# CPU_DRAM.net
KiCad netlist of a schematic drawn in Altium Designer
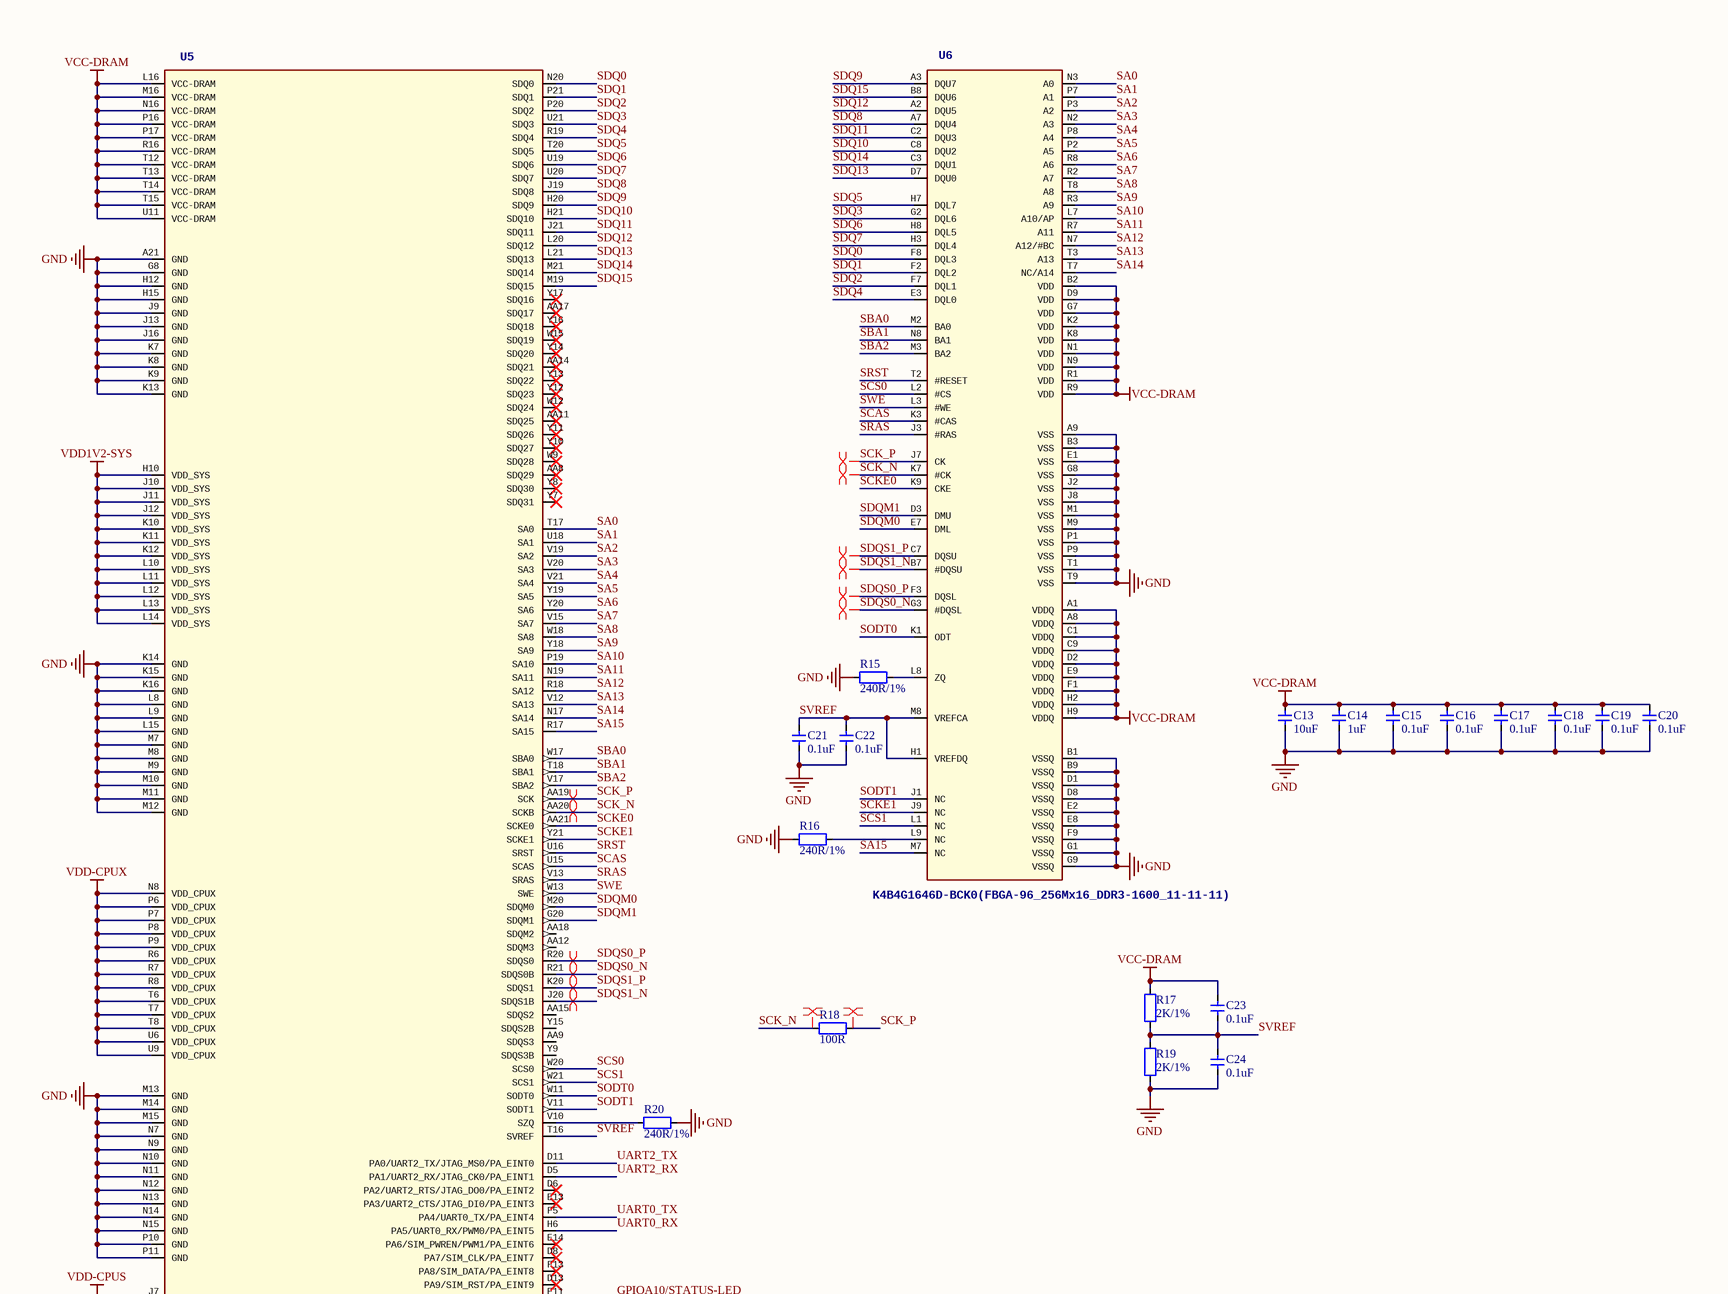
[diagram p0: CPU&DRAM.SchDoc, top]
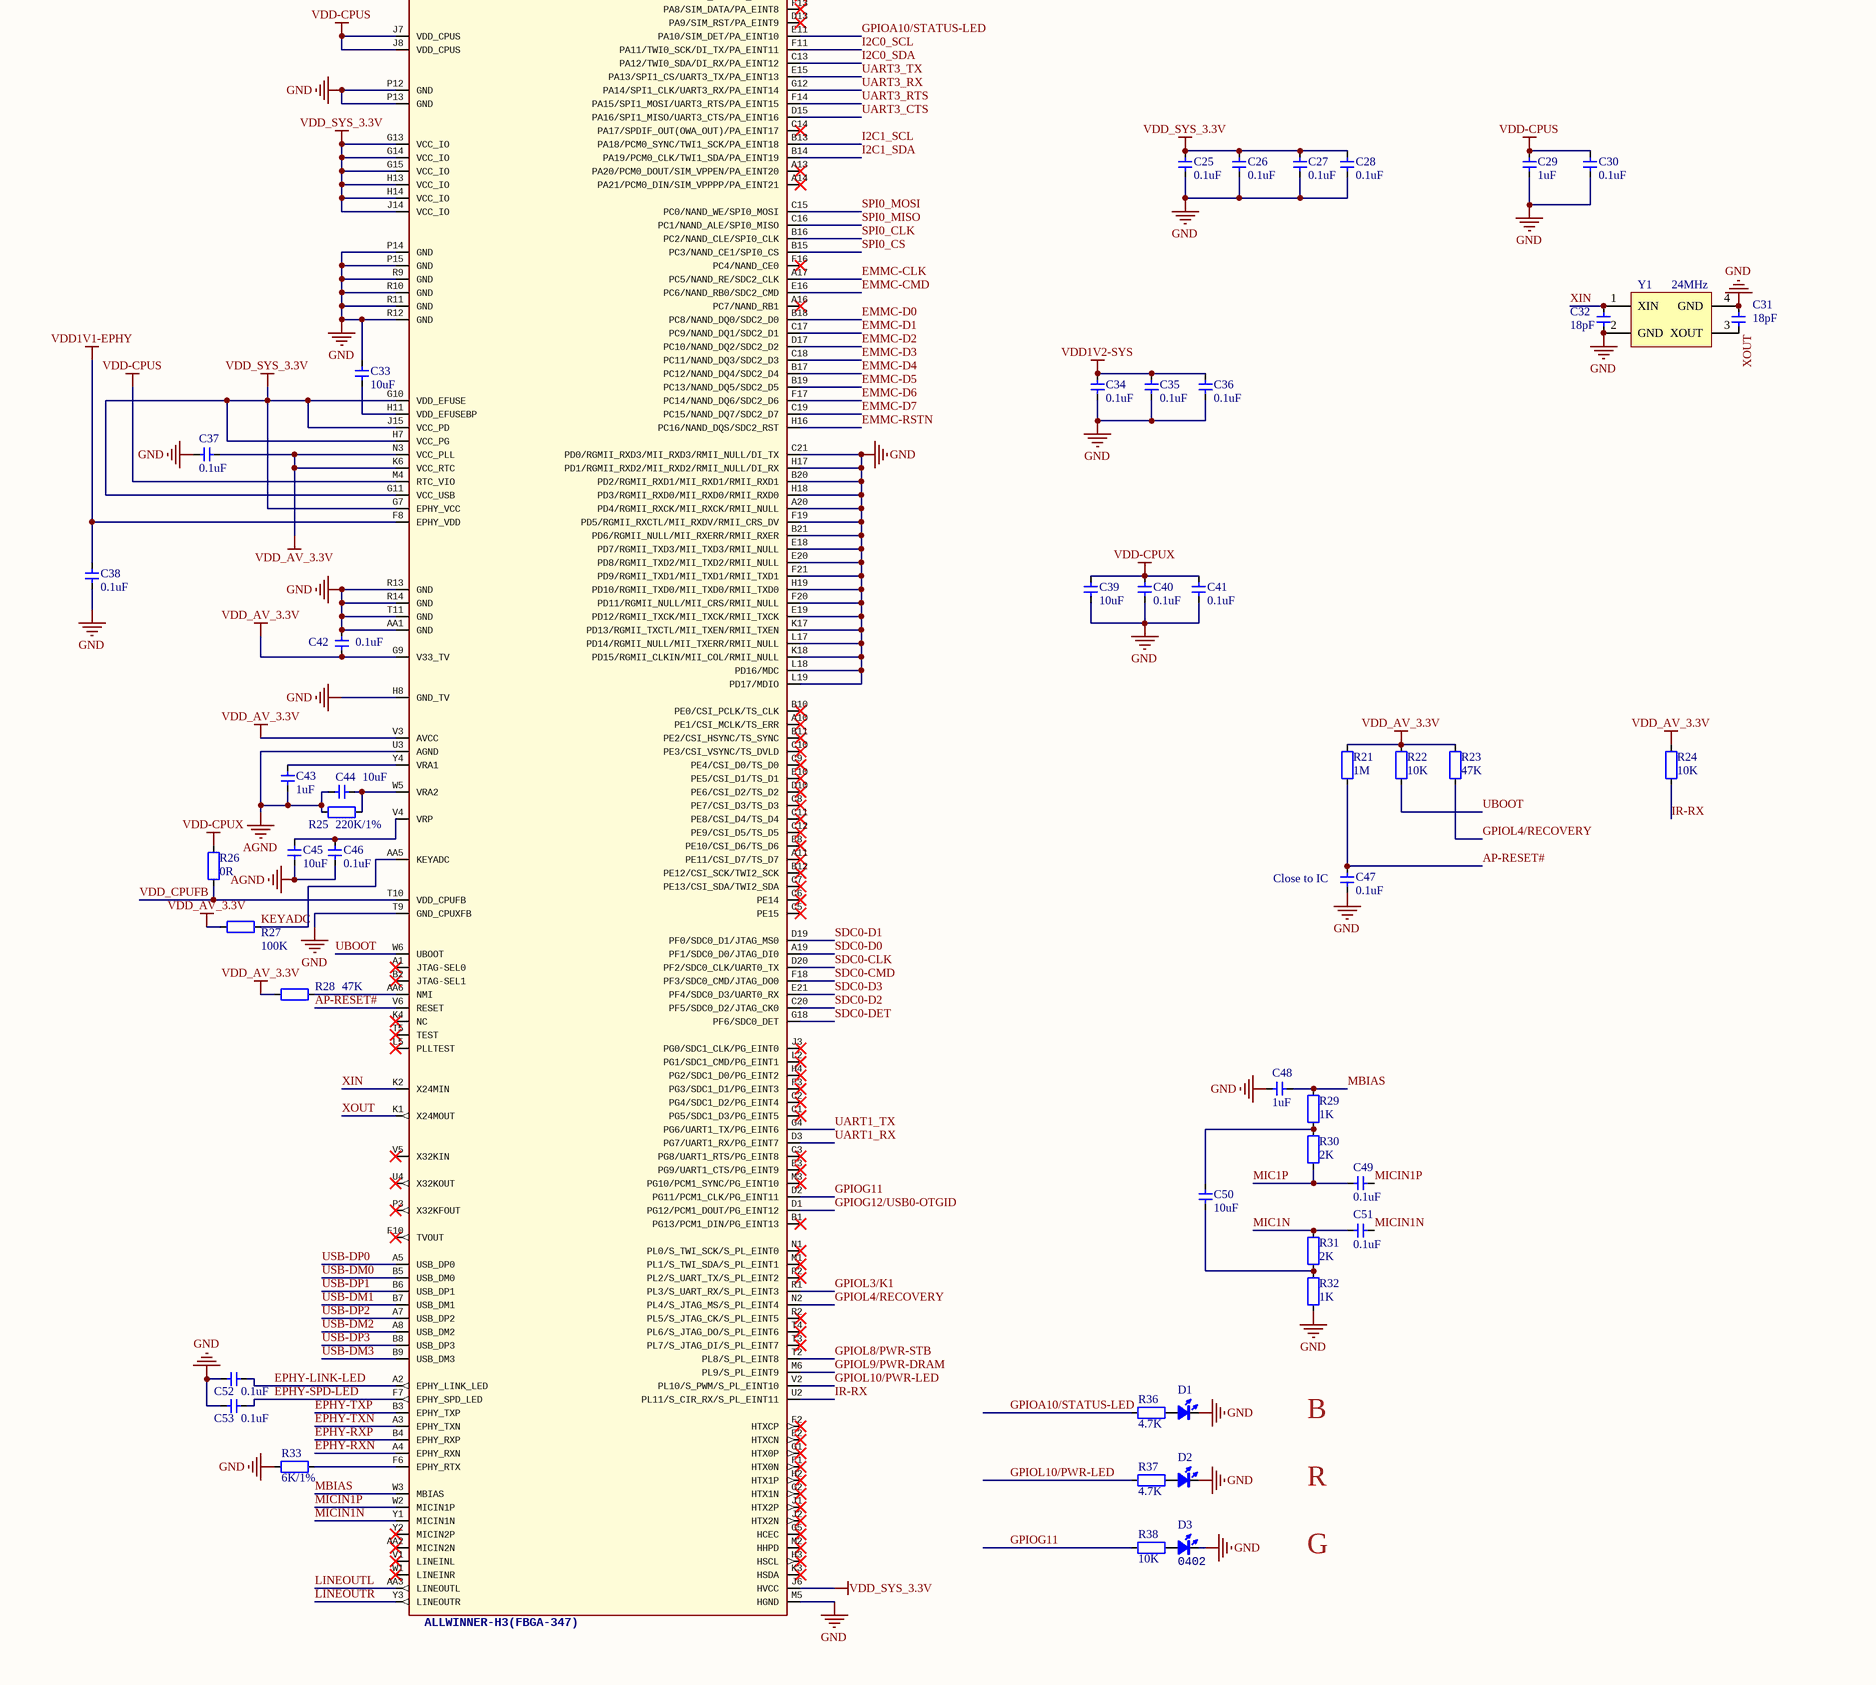
[diagram p1: CPU&DRAM.SchDoc, bottom]

(export (version "E")
  (design (tool "Eeschema 10.0.6"))
  (components
    (comp (ref "C13")
      (value "10uF")
      (footprint "CAP_0402")
      (description "Capacitor")
      (libsource (lib "MyPcbLib") (part "电容-0402"))
    )
    (comp (ref "C14")
      (value "1uF")
      (footprint "CAP_0402")
      (description "Capacitor")
      (libsource (lib "MyPcbLib") (part "电容-0402"))
    )
    (comp (ref "C15")
      (value "0.1uF")
      (footprint "CAP_0402")
      (description "Capacitor")
      (libsource (lib "MyPcbLib") (part "电容-0402"))
    )
    (comp (ref "C16")
      (value "0.1uF")
      (footprint "CAP_0402")
      (description "Capacitor")
      (libsource (lib "MyPcbLib") (part "电容-0402"))
    )
    (comp (ref "C17")
      (value "0.1uF")
      (footprint "CAP_0402")
      (description "Capacitor")
      (libsource (lib "MyPcbLib") (part "电容-0402"))
    )
    (comp (ref "C18")
      (value "0.1uF")
      (footprint "CAP_0402")
      (description "Capacitor")
      (libsource (lib "MyPcbLib") (part "电容-0402"))
    )
    (comp (ref "C19")
      (value "0.1uF")
      (footprint "CAP_0402")
      (description "Capacitor")
      (libsource (lib "MyPcbLib") (part "电容-0402"))
    )
    (comp (ref "C20")
      (value "0.1uF")
      (footprint "CAP_0402")
      (description "Capacitor")
      (libsource (lib "MyPcbLib") (part "电容-0402"))
    )
    (comp (ref "C21")
      (value "0.1uF")
      (footprint "CAP_0402")
      (description "Capacitor")
      (libsource (lib "MyPcbLib") (part "电容-0402"))
    )
    (comp (ref "C22")
      (value "0.1uF")
      (footprint "CAP_0402")
      (description "Capacitor")
      (libsource (lib "MyPcbLib") (part "电容-0402"))
    )
    (comp (ref "C23")
      (value "0.1uF")
      (footprint "CAP_0402")
      (description "Capacitor")
      (libsource (lib "MyPcbLib") (part "电容-0402"))
    )
    (comp (ref "C24")
      (value "0.1uF")
      (footprint "CAP_0402")
      (description "Capacitor")
      (libsource (lib "MyPcbLib") (part "电容-0402"))
    )
    (comp (ref "C25")
      (value "0.1uF")
      (footprint "CAP_0402")
      (description "Capacitor")
      (libsource (lib "MyPcbLib") (part "电容-0402"))
    )
    (comp (ref "C26")
      (value "0.1uF")
      (footprint "CAP_0402")
      (description "Capacitor")
      (libsource (lib "MyPcbLib") (part "电容-0402"))
    )
    (comp (ref "C27")
      (value "0.1uF")
      (footprint "CAP_0402")
      (description "Capacitor")
      (libsource (lib "MyPcbLib") (part "电容-0402"))
    )
    (comp (ref "C28")
      (value "0.1uF")
      (footprint "CAP_0402")
      (description "Capacitor")
      (libsource (lib "MyPcbLib") (part "电容-0402"))
    )
    (comp (ref "C29")
      (value "1uF")
      (footprint "CAP_0402")
      (description "Capacitor")
      (libsource (lib "MyPcbLib") (part "电容-0402"))
    )
    (comp (ref "C30")
      (value "0.1uF")
      (footprint "CAP_0402")
      (description "Capacitor")
      (libsource (lib "MyPcbLib") (part "电容-0402"))
    )
    (comp (ref "C31")
      (value "18pF")
      (footprint "CAP_0402")
      (description "Capacitor")
      (libsource (lib "MyPcbLib") (part "电容-0402"))
    )
    (comp (ref "C32")
      (value "18pF")
      (footprint "CAP_0402")
      (description "Capacitor")
      (libsource (lib "MyPcbLib") (part "电容-0402"))
    )
    (comp (ref "C33")
      (value "10uF")
      (footprint "CAP_0402")
      (description "Capacitor")
      (libsource (lib "MyPcbLib") (part "电容-0402"))
    )
    (comp (ref "C34")
      (value "0.1uF")
      (footprint "CAP_0402")
      (description "Capacitor")
      (libsource (lib "MyPcbLib") (part "电容-0402"))
    )
    (comp (ref "C35")
      (value "0.1uF")
      (footprint "CAP_0402")
      (description "Capacitor")
      (libsource (lib "MyPcbLib") (part "电容-0402"))
    )
    (comp (ref "C36")
      (value "0.1uF")
      (footprint "CAP_0402")
      (description "Capacitor")
      (libsource (lib "MyPcbLib") (part "电容-0402"))
    )
    (comp (ref "C37")
      (value "0.1uF")
      (footprint "CAP_0402")
      (description "Capacitor")
      (libsource (lib "MyPcbLib") (part "电容-0402"))
    )
    (comp (ref "C38")
      (value "0.1uF")
      (footprint "CAP_0402")
      (description "Capacitor")
      (libsource (lib "MyPcbLib") (part "电容-0402"))
    )
    (comp (ref "C39")
      (value "10uF")
      (footprint "CAP_0402")
      (description "Capacitor")
      (libsource (lib "MyPcbLib") (part "电容-0402"))
    )
    (comp (ref "C40")
      (value "0.1uF")
      (footprint "CAP_0402")
      (description "Capacitor")
      (libsource (lib "MyPcbLib") (part "电容-0402"))
    )
    (comp (ref "C41")
      (value "0.1uF")
      (footprint "CAP_0402")
      (description "Capacitor")
      (libsource (lib "MyPcbLib") (part "电容-0402"))
    )
    (comp (ref "C42")
      (value "0.1uF")
      (footprint "CAP_0402")
      (description "Capacitor")
      (libsource (lib "MyPcbLib") (part "电容-0402"))
    )
    (comp (ref "C43")
      (value "1uF")
      (footprint "CAP_0402")
      (description "Capacitor")
      (libsource (lib "MyPcbLib") (part "电容-0402"))
    )
    (comp (ref "C44")
      (value "10uF")
      (footprint "CAP_0402")
      (description "Capacitor")
      (libsource (lib "MyPcbLib") (part "电容-0402"))
    )
    (comp (ref "C45")
      (value "10uF")
      (footprint "CAP_0402")
      (description "Capacitor")
      (libsource (lib "MyPcbLib") (part "电容-0402"))
    )
    (comp (ref "C46")
      (value "0.1uF")
      (footprint "CAP_0402")
      (description "Capacitor")
      (libsource (lib "MyPcbLib") (part "电容-0402"))
    )
    (comp (ref "C47")
      (value "0.1uF")
      (footprint "CAP_0402")
      (description "Capacitor")
      (libsource (lib "MyPcbLib") (part "电容-0402"))
    )
    (comp (ref "C48")
      (value "1uF")
      (footprint "CAP_0402")
      (description "Capacitor")
      (libsource (lib "MyPcbLib") (part "电容-0402"))
    )
    (comp (ref "C49")
      (value "0.1uF")
      (footprint "CAP_0402")
      (description "Capacitor")
      (libsource (lib "MyPcbLib") (part "电容-0402"))
    )
    (comp (ref "C50")
      (value "10uF")
      (footprint "CAP_0402")
      (description "Capacitor")
      (libsource (lib "MyPcbLib") (part "电容-0402"))
    )
    (comp (ref "C51")
      (value "0.1uF")
      (footprint "CAP_0402")
      (description "Capacitor")
      (libsource (lib "MyPcbLib") (part "电容-0402"))
    )
    (comp (ref "C52")
      (value "0.1uF")
      (footprint "CAP_0402")
      (description "Capacitor")
      (libsource (lib "MyPcbLib") (part "电容-0402"))
    )
    (comp (ref "C53")
      (value "0.1uF")
      (footprint "CAP_0402")
      (description "Capacitor")
      (libsource (lib "MyPcbLib") (part "电容-0402"))
    )
    (comp (ref "D1")
      (value "color?")
      (footprint "LED_0402_BLUE")
      (description "LED")
      (libsource (lib "KitSprout") (part "LED_0402"))
    )
    (comp (ref "D2")
      (value "color?")
      (footprint "LED_0402_RED")
      (description "LED")
      (libsource (lib "KitSprout") (part "LED_0402"))
    )
    (comp (ref "D3")
      (value "color?")
      (footprint "LED_0402_G")
      (description "LED")
      (fields (field (name "TYPE") "0402"))
      (libsource (lib "KitSprout") (part "LED_0402"))
    )
    (comp (ref "R15")
      (value "240R/1%")
      (footprint "RES_0402")
      (description "Resistor")
      (libsource (lib "") (part "电阻-0402_1"))
    )
    (comp (ref "R16")
      (value "240R/1%")
      (footprint "RES_0402")
      (description "Resistor")
      (libsource (lib "") (part "电阻-0402_1"))
    )
    (comp (ref "R17")
      (value "2K/1%")
      (footprint "RES_0402")
      (description "Resistor")
      (libsource (lib "MyPcbLib") (part "电阻-0402"))
    )
    (comp (ref "R18")
      (value "100R")
      (footprint "RES_0402")
      (description "Resistor")
      (libsource (lib "") (part "电阻-0402_2"))
    )
    (comp (ref "R19")
      (value "2K/1%")
      (footprint "RES_0402")
      (description "Resistor")
      (libsource (lib "MyPcbLib") (part "电阻-0402"))
    )
    (comp (ref "R20")
      (value "240R/1%")
      (footprint "RES_0402")
      (description "Resistor")
      (libsource (lib "") (part "电阻-0402_2"))
    )
    (comp (ref "R21")
      (value "1M")
      (footprint "RES_0402")
      (description "Resistor")
      (libsource (lib "MyPcbLib") (part "电阻-0402"))
    )
    (comp (ref "R22")
      (value "10K")
      (footprint "RES_0402")
      (description "Resistor")
      (libsource (lib "MyPcbLib") (part "电阻-0402"))
    )
    (comp (ref "R23")
      (value "47K")
      (footprint "RES_0402")
      (description "Resistor")
      (libsource (lib "MyPcbLib") (part "电阻-0402"))
    )
    (comp (ref "R24")
      (value "10K")
      (footprint "RES_0402")
      (description "Resistor")
      (libsource (lib "MyPcbLib") (part "电阻-0402"))
    )
    (comp (ref "R25")
      (value "220K/1%")
      (footprint "RES_0402")
      (description "Resistor")
      (libsource (lib "") (part "电阻-0402_2"))
    )
    (comp (ref "R26")
      (value "0R")
      (footprint "RES_0402")
      (description "Resistor")
      (libsource (lib "MyPcbLib") (part "电阻-0402"))
    )
    (comp (ref "R27")
      (value "100K")
      (footprint "RES_0402")
      (description "Resistor")
      (libsource (lib "") (part "电阻-0402_2"))
    )
    (comp (ref "R28")
      (value "47K")
      (footprint "RES_0402")
      (description "Resistor")
      (libsource (lib "") (part "电阻-0402_2"))
    )
    (comp (ref "R29")
      (value "1K")
      (footprint "RES_0402")
      (description "Resistor")
      (libsource (lib "MyPcbLib") (part "电阻-0402"))
    )
    (comp (ref "R30")
      (value "2K")
      (footprint "RES_0402")
      (description "Resistor")
      (libsource (lib "MyPcbLib") (part "电阻-0402"))
    )
    (comp (ref "R31")
      (value "2K")
      (footprint "RES_0402")
      (description "Resistor")
      (libsource (lib "MyPcbLib") (part "电阻-0402"))
    )
    (comp (ref "R32")
      (value "1K")
      (footprint "RES_0402")
      (description "Resistor")
      (libsource (lib "MyPcbLib") (part "电阻-0402"))
    )
    (comp (ref "R33")
      (value "6K/1%")
      (footprint "RES_0402")
      (description "Resistor")
      (libsource (lib "") (part "电阻-0402_2"))
    )
    (comp (ref "R36")
      (value "4.7K")
      (footprint "RES_0402")
      (description "Resistor")
      (libsource (lib "") (part "电阻-0402_2"))
    )
    (comp (ref "R37")
      (value "4.7K")
      (footprint "RES_0402")
      (description "Resistor")
      (libsource (lib "") (part "电阻-0402_2"))
    )
    (comp (ref "R38")
      (value "10K")
      (footprint "RES_0402")
      (description "Resistor")
      (libsource (lib "") (part "电阻-0402_2"))
    )
    (comp (ref "U5")
      (value "ALLWINNER-H3(FBGA-347)")
      (footprint "FBGA-347 - duplicate")
      (libsource (lib "mLib") (part "ALLWINNER-H3(FBGA-347)"))
    )
    (comp (ref "U6")
      (value "K4B4G1646D-BCK0(FBGA-96_256Mx16_DDR3-1600_11-11-11)")
      (footprint "FBGA96(HYNIX_SAMSUNG_512MX16_DDR3)")
      (libsource (lib "mLib") (part "K4B8G1646Q-MYK0(FBGA-96_512MX16_DDR3-1600)"))
    )
    (comp (ref "Y1")
      (value "24MHz")
      (footprint "晶振2520")
      (description "2520无源")
      (fields (field (name "MF") "ECS International") (field (name "MP") "ECS-3225S30-240-EN-TR"))
      (libsource (lib "MyPcbLib") (part "晶振-4Pin-无源"))
    )
  )
  (nets
    (net (code "1") (name "/AP-RESET#") (class "Default")
      (node (ref "C47") (pin "2") (pinfunction "2_2") (pintype "passive"))
      (node (ref "R21") (pin "1") (pinfunction "1_1") (pintype "passive"))
      (node (ref "U5") (pin "V6") (pinfunction "RESET_V6") (pintype "passive"))
    )
    (net (code "2") (name "/EMMC-CLK") (class "Default")
      (node (ref "U5") (pin "A17") (pinfunction "PC5/NAND_RE/SDC2_CLK_A17") (pintype "passive"))
    )
    (net (code "3") (name "/EMMC-CMD") (class "Default")
      (node (ref "U5") (pin "E16") (pinfunction "PC6/NAND_RB0/SDC2_CMD_E16") (pintype "passive"))
    )
    (net (code "4") (name "/EMMC-D0") (class "Default")
      (node (ref "U5") (pin "B18") (pinfunction "PC8/NAND_DQ0/SDC2_D0_B18") (pintype "passive"))
    )
    (net (code "5") (name "/EMMC-D1") (class "Default")
      (node (ref "U5") (pin "C17") (pinfunction "PC9/NAND_DQ1/SDC2_D1_C17") (pintype "passive"))
    )
    (net (code "6") (name "/EMMC-D2") (class "Default")
      (node (ref "U5") (pin "D17") (pinfunction "PC10/NAND_DQ2/SDC2_D2_D17") (pintype "passive"))
    )
    (net (code "7") (name "/EMMC-D3") (class "Default")
      (node (ref "U5") (pin "C18") (pinfunction "PC11/NAND_DQ3/SDC2_D3_C18") (pintype "passive"))
    )
    (net (code "8") (name "/EMMC-D4") (class "Default")
      (node (ref "U5") (pin "B17") (pinfunction "PC12/NAND_DQ4/SDC2_D4_B17") (pintype "passive"))
    )
    (net (code "9") (name "/EMMC-D5") (class "Default")
      (node (ref "U5") (pin "B19") (pinfunction "PC13/NAND_DQ5/SDC2_D5_B19") (pintype "passive"))
    )
    (net (code "10") (name "/EMMC-D6") (class "Default")
      (node (ref "U5") (pin "F17") (pinfunction "PC14/NAND_DQ6/SDC2_D6_F17") (pintype "passive"))
    )
    (net (code "11") (name "/EMMC-D7") (class "Default")
      (node (ref "U5") (pin "C19") (pinfunction "PC15/NAND_DQ7/SDC2_D7_C19") (pintype "passive"))
    )
    (net (code "12") (name "/EMMC-RSTN") (class "Default")
      (node (ref "U5") (pin "H16") (pinfunction "PC16/NAND_DQS/SDC2_RST_H16") (pintype "passive"))
    )
    (net (code "13") (name "/EPHY-LINK-LED") (class "Default")
      (node (ref "C52") (pin "2") (pinfunction "2_2") (pintype "passive"))
      (node (ref "U5") (pin "A2") (pinfunction "EPHY_LINK_LED_A2") (pintype "output"))
    )
    (net (code "14") (name "/EPHY-RXN") (class "Default")
      (node (ref "U5") (pin "A4") (pinfunction "EPHY_RXN_A4") (pintype "passive"))
    )
    (net (code "15") (name "/EPHY-RXP") (class "Default")
      (node (ref "U5") (pin "B4") (pinfunction "EPHY_RXP_B4") (pintype "passive"))
    )
    (net (code "16") (name "/EPHY-SPD-LED") (class "Default")
      (node (ref "C53") (pin "2") (pinfunction "2_2") (pintype "passive"))
      (node (ref "U5") (pin "F7") (pinfunction "EPHY_SPD_LED_F7") (pintype "output"))
    )
    (net (code "17") (name "/EPHY-TXN") (class "Default")
      (node (ref "U5") (pin "A3") (pinfunction "EPHY_TXN_A3") (pintype "passive"))
    )
    (net (code "18") (name "/EPHY-TXP") (class "Default")
      (node (ref "U5") (pin "B3") (pinfunction "EPHY_TXP_B3") (pintype "passive"))
    )
    (net (code "19") (name "/GPIOA10{slash}STATUS-LED") (class "Default")
      (node (ref "R36") (pin "1") (pinfunction "1_1") (pintype "passive"))
      (node (ref "U5") (pin "E11") (pinfunction "PA10/SIM_DET/PA_EINT10_E11") (pintype "passive"))
    )
    (net (code "20") (name "/GPIOG11") (class "Default")
      (node (ref "R38") (pin "1") (pinfunction "1_1") (pintype "passive"))
      (node (ref "U5") (pin "D2") (pinfunction "PG11/PCM1_CLK/PG_EINT11_D2") (pintype "passive"))
    )
    (net (code "21") (name "/GPIOG12{slash}USB0-OTGID") (class "Default")
      (node (ref "U5") (pin "D1") (pinfunction "PG12/PCM1_DOUT/PG_EINT12_D1") (pintype "passive"))
    )
    (net (code "22") (name "/GPIOL3{slash}K1") (class "Default")
      (node (ref "U5") (pin "R1") (pinfunction "PL3/S_UART_RX/S_PL_EINT3_R1") (pintype "passive"))
    )
    (net (code "23") (name "/GPIOL4{slash}RECOVERY") (class "Default")
      (node (ref "R23") (pin "1") (pinfunction "1_1") (pintype "passive"))
      (node (ref "U5") (pin "N2") (pinfunction "PL4/S_JTAG_MS/S_PL_EINT4_N2") (pintype "passive"))
    )
    (net (code "24") (name "/GPIOL8{slash}PWR-STB") (class "Default")
      (node (ref "U5") (pin "T2") (pinfunction "PL8/S_PL_EINT8_T2") (pintype "passive"))
    )
    (net (code "25") (name "/GPIOL9{slash}PWR-DRAM") (class "Default")
      (node (ref "U5") (pin "M6") (pinfunction "PL9/S_PL_EINT9_M6") (pintype "passive"))
    )
    (net (code "26") (name "/GPIOL10{slash}PWR-LED") (class "Default")
      (node (ref "R37") (pin "1") (pinfunction "1_1") (pintype "passive"))
      (node (ref "U5") (pin "V2") (pinfunction "PL10/S_PWM/S_PL_EINT10_V2") (pintype "passive"))
    )
    (net (code "27") (name "/I2C0_SCL") (class "Default")
      (node (ref "U5") (pin "F11") (pinfunction "PA11/TWI0_SCK/DI_TX/PA_EINT11_F11") (pintype "passive"))
    )
    (net (code "28") (name "/I2C0_SDA") (class "Default")
      (node (ref "U5") (pin "C13") (pinfunction "PA12/TWI0_SDA/DI_RX/PA_EINT12_C13") (pintype "passive"))
    )
    (net (code "29") (name "/I2C1_SCL") (class "Default")
      (node (ref "U5") (pin "B13") (pinfunction "PA18/PCM0_SYNC/TWI1_SCK/PA_EINT18_B13") (pintype "passive"))
    )
    (net (code "30") (name "/I2C1_SDA") (class "Default")
      (node (ref "U5") (pin "B14") (pinfunction "PA19/PCM0_CLK/TWI1_SDA/PA_EINT19_B14") (pintype "passive"))
    )
    (net (code "31") (name "/IR-RX") (class "Default")
      (node (ref "R24") (pin "1") (pinfunction "1_1") (pintype "passive"))
      (node (ref "U5") (pin "U2") (pinfunction "PL11/S_CIR_RX/S_PL_EINT11_U2") (pintype "passive"))
    )
    (net (code "32") (name "/KEYADC") (class "Default")
      (node (ref "R27") (pin "2") (pinfunction "2_2") (pintype "passive"))
      (node (ref "U5") (pin "AA5") (pinfunction "KEYADC_AA5") (pintype "passive"))
    )
    (net (code "33") (name "/LINEOUTL") (class "Default")
      (node (ref "U5") (pin "AA3") (pinfunction "LINEOUTL_AA3") (pintype "output"))
    )
    (net (code "34") (name "/LINEOUTR") (class "Default")
      (node (ref "U5") (pin "Y3") (pinfunction "LINEOUTR_Y3") (pintype "output"))
    )
    (net (code "35") (name "/MBIAS") (class "Default")
      (node (ref "C48") (pin "1") (pinfunction "1_1") (pintype "passive"))
      (node (ref "R29") (pin "2") (pinfunction "2_2") (pintype "passive"))
      (node (ref "U5") (pin "W3") (pinfunction "MBIAS_W3") (pintype "passive"))
    )
    (net (code "36") (name "/MIC1N") (class "Default")
      (node (ref "C51") (pin "2") (pinfunction "2_2") (pintype "passive"))
      (node (ref "R31") (pin "2") (pinfunction "2_2") (pintype "passive"))
    )
    (net (code "37") (name "/MIC1P") (class "Default")
      (node (ref "C49") (pin "2") (pinfunction "2_2") (pintype "passive"))
      (node (ref "R30") (pin "1") (pinfunction "1_1") (pintype "passive"))
    )
    (net (code "38") (name "/MICIN1N") (class "Default")
      (node (ref "C51") (pin "1") (pinfunction "1_1") (pintype "passive"))
      (node (ref "U5") (pin "Y1") (pinfunction "MICIN1N_Y1") (pintype "passive"))
    )
    (net (code "39") (name "/MICIN1P") (class "Default")
      (node (ref "C49") (pin "1") (pinfunction "1_1") (pintype "passive"))
      (node (ref "U5") (pin "W2") (pinfunction "MICIN1P_W2") (pintype "passive"))
    )
    (net (code "40") (name "/SA0") (class "Default")
      (node (ref "U5") (pin "T17") (pinfunction "SA0_T17") (pintype "passive"))
      (node (ref "U6") (pin "N3") (pinfunction "A0_N3") (pintype "passive"))
    )
    (net (code "41") (name "/SA1") (class "Default")
      (node (ref "U5") (pin "U18") (pinfunction "SA1_U18") (pintype "passive"))
      (node (ref "U6") (pin "P7") (pinfunction "A1_P7") (pintype "passive"))
    )
    (net (code "42") (name "/SA2") (class "Default")
      (node (ref "U5") (pin "V19") (pinfunction "SA2_V19") (pintype "passive"))
      (node (ref "U6") (pin "P3") (pinfunction "A2_P3") (pintype "passive"))
    )
    (net (code "43") (name "/SA3") (class "Default")
      (node (ref "U5") (pin "V20") (pinfunction "SA3_V20") (pintype "passive"))
      (node (ref "U6") (pin "N2") (pinfunction "A3_N2") (pintype "passive"))
    )
    (net (code "44") (name "/SA4") (class "Default")
      (node (ref "U5") (pin "V21") (pinfunction "SA4_V21") (pintype "passive"))
      (node (ref "U6") (pin "P8") (pinfunction "A4_P8") (pintype "passive"))
    )
    (net (code "45") (name "/SA5") (class "Default")
      (node (ref "U5") (pin "Y19") (pinfunction "SA5_Y19") (pintype "passive"))
      (node (ref "U6") (pin "P2") (pinfunction "A5_P2") (pintype "passive"))
    )
    (net (code "46") (name "/SA6") (class "Default")
      (node (ref "U5") (pin "Y20") (pinfunction "SA6_Y20") (pintype "passive"))
      (node (ref "U6") (pin "R8") (pinfunction "A6_R8") (pintype "passive"))
    )
    (net (code "47") (name "/SA7") (class "Default")
      (node (ref "U5") (pin "V15") (pinfunction "SA7_V15") (pintype "passive"))
      (node (ref "U6") (pin "R2") (pinfunction "A7_R2") (pintype "passive"))
    )
    (net (code "48") (name "/SA8") (class "Default")
      (node (ref "U5") (pin "W18") (pinfunction "SA8_W18") (pintype "passive"))
      (node (ref "U6") (pin "T8") (pinfunction "A8_T8") (pintype "passive"))
    )
    (net (code "49") (name "/SA9") (class "Default")
      (node (ref "U5") (pin "Y18") (pinfunction "SA9_Y18") (pintype "passive"))
      (node (ref "U6") (pin "R3") (pinfunction "A9_R3") (pintype "passive"))
    )
    (net (code "50") (name "/SA10") (class "Default")
      (node (ref "U5") (pin "P19") (pinfunction "SA10_P19") (pintype "passive"))
      (node (ref "U6") (pin "L7") (pinfunction "A10/AP_L7") (pintype "passive"))
    )
    (net (code "51") (name "/SA11") (class "Default")
      (node (ref "U5") (pin "N19") (pinfunction "SA11_N19") (pintype "passive"))
      (node (ref "U6") (pin "R7") (pinfunction "A11_R7") (pintype "passive"))
    )
    (net (code "52") (name "/SA12") (class "Default")
      (node (ref "U5") (pin "R18") (pinfunction "SA12_R18") (pintype "passive"))
      (node (ref "U6") (pin "N7") (pinfunction "A12/#BC_N7") (pintype "passive"))
    )
    (net (code "53") (name "/SA13") (class "Default")
      (node (ref "U5") (pin "V12") (pinfunction "SA13_V12") (pintype "passive"))
      (node (ref "U6") (pin "T3") (pinfunction "A13_T3") (pintype "passive"))
    )
    (net (code "54") (name "/SA14") (class "Default")
      (node (ref "U5") (pin "N17") (pinfunction "SA14_N17") (pintype "passive"))
      (node (ref "U6") (pin "T7") (pinfunction "NC/A14_T7") (pintype "passive"))
    )
    (net (code "55") (name "/SA15") (class "Default")
      (node (ref "U5") (pin "R17") (pinfunction "SA15_R17") (pintype "passive"))
      (node (ref "U6") (pin "M7") (pinfunction "NC_M7") (pintype "passive"))
    )
    (net (code "56") (name "/SBA0") (class "Default")
      (node (ref "U5") (pin "W17") (pinfunction "SBA0_W17") (pintype "output"))
      (node (ref "U6") (pin "M2") (pinfunction "BA0_M2") (pintype "passive"))
    )
    (net (code "57") (name "/SBA1") (class "Default")
      (node (ref "U5") (pin "T18") (pinfunction "SBA1_T18") (pintype "output"))
      (node (ref "U6") (pin "N8") (pinfunction "BA1_N8") (pintype "passive"))
    )
    (net (code "58") (name "/SBA2") (class "Default")
      (node (ref "U5") (pin "V17") (pinfunction "SBA2_V17") (pintype "output"))
      (node (ref "U6") (pin "M3") (pinfunction "BA2_M3") (pintype "passive"))
    )
    (net (code "59") (name "/SCAS") (class "Default")
      (node (ref "U5") (pin "U15") (pinfunction "SCAS_U15") (pintype "output"))
      (node (ref "U6") (pin "K3") (pinfunction "#CAS_K3") (pintype "passive"))
    )
    (net (code "60") (name "/SCKE0") (class "Default")
      (node (ref "U5") (pin "AA21") (pinfunction "SCKE0_AA21") (pintype "output"))
      (node (ref "U6") (pin "K9") (pinfunction "CKE_K9") (pintype "passive"))
    )
    (net (code "61") (name "/SCKE1") (class "Default")
      (node (ref "U5") (pin "Y21") (pinfunction "SCKE1_Y21") (pintype "output"))
      (node (ref "U6") (pin "J9") (pinfunction "NC_J9") (pintype "passive"))
    )
    (net (code "62") (name "/SCK_N") (class "Default")
      (node (ref "R18") (pin "1") (pinfunction "1_1") (pintype "passive"))
      (node (ref "U5") (pin "AA20") (pinfunction "SCKB_AA20") (pintype "output"))
      (node (ref "U6") (pin "K7") (pinfunction "#CK_K7") (pintype "passive"))
    )
    (net (code "63") (name "/SCK_P") (class "Default")
      (node (ref "R18") (pin "2") (pinfunction "2_2") (pintype "passive"))
      (node (ref "U5") (pin "AA19") (pinfunction "SCK_AA19") (pintype "output"))
      (node (ref "U6") (pin "J7") (pinfunction "CK_J7") (pintype "passive"))
    )
    (net (code "64") (name "/SCS0") (class "Default")
      (node (ref "U5") (pin "W20") (pinfunction "SCS0_W20") (pintype "output"))
      (node (ref "U6") (pin "L2") (pinfunction "#CS_L2") (pintype "passive"))
    )
    (net (code "65") (name "/SCS1") (class "Default")
      (node (ref "U5") (pin "W21") (pinfunction "SCS1_W21") (pintype "output"))
      (node (ref "U6") (pin "L1") (pinfunction "NC_L1") (pintype "passive"))
    )
    (net (code "66") (name "/SDC0-CLK") (class "Default")
      (node (ref "U5") (pin "D20") (pinfunction "PF2/SDC0_CLK/UART0_TX_D20") (pintype "passive"))
    )
    (net (code "67") (name "/SDC0-CMD") (class "Default")
      (node (ref "U5") (pin "F18") (pinfunction "PF3/SDC0_CMD/JTAG_DO0_F18") (pintype "passive"))
    )
    (net (code "68") (name "/SDC0-D0") (class "Default")
      (node (ref "U5") (pin "A19") (pinfunction "PF1/SDC0_D0/JTAG_DI0_A19") (pintype "passive"))
    )
    (net (code "69") (name "/SDC0-D1") (class "Default")
      (node (ref "U5") (pin "D19") (pinfunction "PF0/SDC0_D1/JTAG_MS0_D19") (pintype "passive"))
    )
    (net (code "70") (name "/SDC0-D2") (class "Default")
      (node (ref "U5") (pin "C20") (pinfunction "PF5/SDC0_D2/JTAG_CK0_C20") (pintype "passive"))
    )
    (net (code "71") (name "/SDC0-D3") (class "Default")
      (node (ref "U5") (pin "E21") (pinfunction "PF4/SDC0_D3/UART0_RX_E21") (pintype "passive"))
    )
    (net (code "72") (name "/SDC0-DET") (class "Default")
      (node (ref "U5") (pin "G18") (pinfunction "PF6/SDC0_DET_G18") (pintype "passive"))
    )
    (net (code "73") (name "/SDQ0") (class "Default")
      (node (ref "U5") (pin "N20") (pinfunction "SDQ0_N20") (pintype "passive"))
      (node (ref "U6") (pin "F8") (pinfunction "DQL3_F8") (pintype "passive"))
    )
    (net (code "74") (name "/SDQ1") (class "Default")
      (node (ref "U5") (pin "P21") (pinfunction "SDQ1_P21") (pintype "passive"))
      (node (ref "U6") (pin "F2") (pinfunction "DQL2_F2") (pintype "passive"))
    )
    (net (code "75") (name "/SDQ2") (class "Default")
      (node (ref "U5") (pin "P20") (pinfunction "SDQ2_P20") (pintype "passive"))
      (node (ref "U6") (pin "F7") (pinfunction "DQL1_F7") (pintype "passive"))
    )
    (net (code "76") (name "/SDQ3") (class "Default")
      (node (ref "U5") (pin "U21") (pinfunction "SDQ3_U21") (pintype "passive"))
      (node (ref "U6") (pin "G2") (pinfunction "DQL6_G2") (pintype "passive"))
    )
    (net (code "77") (name "/SDQ4") (class "Default")
      (node (ref "U5") (pin "R19") (pinfunction "SDQ4_R19") (pintype "passive"))
      (node (ref "U6") (pin "E3") (pinfunction "DQL0_E3") (pintype "passive"))
    )
    (net (code "78") (name "/SDQ5") (class "Default")
      (node (ref "U5") (pin "T20") (pinfunction "SDQ5_T20") (pintype "passive"))
      (node (ref "U6") (pin "H7") (pinfunction "DQL7_H7") (pintype "passive"))
    )
    (net (code "79") (name "/SDQ6") (class "Default")
      (node (ref "U5") (pin "U19") (pinfunction "SDQ6_U19") (pintype "passive"))
      (node (ref "U6") (pin "H8") (pinfunction "DQL5_H8") (pintype "passive"))
    )
    (net (code "80") (name "/SDQ7") (class "Default")
      (node (ref "U5") (pin "U20") (pinfunction "SDQ7_U20") (pintype "passive"))
      (node (ref "U6") (pin "H3") (pinfunction "DQL4_H3") (pintype "passive"))
    )
    (net (code "81") (name "/SDQ8") (class "Default")
      (node (ref "U5") (pin "J19") (pinfunction "SDQ8_J19") (pintype "passive"))
      (node (ref "U6") (pin "A7") (pinfunction "DQU4_A7") (pintype "passive"))
    )
    (net (code "82") (name "/SDQ9") (class "Default")
      (node (ref "U5") (pin "H20") (pinfunction "SDQ9_H20") (pintype "passive"))
      (node (ref "U6") (pin "A3") (pinfunction "DQU7_A3") (pintype "passive"))
    )
    (net (code "83") (name "/SDQ10") (class "Default")
      (node (ref "U5") (pin "H21") (pinfunction "SDQ10_H21") (pintype "passive"))
      (node (ref "U6") (pin "C8") (pinfunction "DQU2_C8") (pintype "passive"))
    )
    (net (code "84") (name "/SDQ11") (class "Default")
      (node (ref "U5") (pin "J21") (pinfunction "SDQ11_J21") (pintype "passive"))
      (node (ref "U6") (pin "C2") (pinfunction "DQU3_C2") (pintype "passive"))
    )
    (net (code "85") (name "/SDQ12") (class "Default")
      (node (ref "U5") (pin "L20") (pinfunction "SDQ12_L20") (pintype "passive"))
      (node (ref "U6") (pin "A2") (pinfunction "DQU5_A2") (pintype "passive"))
    )
    (net (code "86") (name "/SDQ13") (class "Default")
      (node (ref "U5") (pin "L21") (pinfunction "SDQ13_L21") (pintype "passive"))
      (node (ref "U6") (pin "D7") (pinfunction "DQU0_D7") (pintype "passive"))
    )
    (net (code "87") (name "/SDQ14") (class "Default")
      (node (ref "U5") (pin "M21") (pinfunction "SDQ14_M21") (pintype "passive"))
      (node (ref "U6") (pin "C3") (pinfunction "DQU1_C3") (pintype "passive"))
    )
    (net (code "88") (name "/SDQ15") (class "Default")
      (node (ref "U5") (pin "M19") (pinfunction "SDQ15_M19") (pintype "passive"))
      (node (ref "U6") (pin "B8") (pinfunction "DQU6_B8") (pintype "passive"))
    )
    (net (code "89") (name "/SDQM0") (class "Default")
      (node (ref "U5") (pin "M20") (pinfunction "SDQM0_M20") (pintype "output"))
      (node (ref "U6") (pin "E7") (pinfunction "DML_E7") (pintype "passive"))
    )
    (net (code "90") (name "/SDQM1") (class "Default")
      (node (ref "U5") (pin "G20") (pinfunction "SDQM1_G20") (pintype "output"))
      (node (ref "U6") (pin "D3") (pinfunction "DMU_D3") (pintype "passive"))
    )
    (net (code "91") (name "/SDQS0_N") (class "Default")
      (node (ref "U5") (pin "R21") (pinfunction "SDQS0B_R21") (pintype "passive"))
      (node (ref "U6") (pin "G3") (pinfunction "#DQSL_G3") (pintype "passive"))
    )
    (net (code "92") (name "/SDQS0_P") (class "Default")
      (node (ref "U5") (pin "R20") (pinfunction "SDQS0_R20") (pintype "passive"))
      (node (ref "U6") (pin "F3") (pinfunction "DQSL_F3") (pintype "passive"))
    )
    (net (code "93") (name "/SDQS1_N") (class "Default")
      (node (ref "U5") (pin "J20") (pinfunction "SDQS1B_J20") (pintype "passive"))
      (node (ref "U6") (pin "B7") (pinfunction "#DQSU_B7") (pintype "passive"))
    )
    (net (code "94") (name "/SDQS1_P") (class "Default")
      (node (ref "U5") (pin "K20") (pinfunction "SDQS1_K20") (pintype "passive"))
      (node (ref "U6") (pin "C7") (pinfunction "DQSU_C7") (pintype "passive"))
    )
    (net (code "95") (name "/SODT0") (class "Default")
      (node (ref "U5") (pin "W11") (pinfunction "SODT0_W11") (pintype "output"))
      (node (ref "U6") (pin "K1") (pinfunction "ODT_K1") (pintype "passive"))
    )
    (net (code "96") (name "/SODT1") (class "Default")
      (node (ref "U5") (pin "V11") (pinfunction "SODT1_V11") (pintype "output"))
      (node (ref "U6") (pin "J1") (pinfunction "NC_J1") (pintype "passive"))
    )
    (net (code "97") (name "/SPI0_CLK") (class "Default")
      (node (ref "U5") (pin "B16") (pinfunction "PC2/NAND_CLE/SPI0_CLK_B16") (pintype "passive"))
    )
    (net (code "98") (name "/SPI0_CS") (class "Default")
      (node (ref "U5") (pin "B15") (pinfunction "PC3/NAND_CE1/SPI0_CS_B15") (pintype "passive"))
    )
    (net (code "99") (name "/SPI0_MISO") (class "Default")
      (node (ref "U5") (pin "C16") (pinfunction "PC1/NAND_ALE/SPI0_MISO_C16") (pintype "passive"))
    )
    (net (code "100") (name "/SPI0_MOSI") (class "Default")
      (node (ref "U5") (pin "C15") (pinfunction "PC0/NAND_WE/SPI0_MOSI_C15") (pintype "passive"))
    )
    (net (code "101") (name "/SRAS") (class "Default")
      (node (ref "U5") (pin "V13") (pinfunction "SRAS_V13") (pintype "output"))
      (node (ref "U6") (pin "J3") (pinfunction "#RAS_J3") (pintype "passive"))
    )
    (net (code "102") (name "/SRST") (class "Default")
      (node (ref "U5") (pin "U16") (pinfunction "SRST_U16") (pintype "output"))
      (node (ref "U6") (pin "T2") (pinfunction "#RESET_T2") (pintype "passive"))
    )
    (net (code "103") (name "/SVREF") (class "Default")
      (node (ref "C21") (pin "2") (pinfunction "2_2") (pintype "passive"))
      (node (ref "C22") (pin "2") (pinfunction "2_2") (pintype "passive"))
      (node (ref "C23") (pin "1") (pinfunction "1_1") (pintype "passive"))
      (node (ref "C24") (pin "2") (pinfunction "2_2") (pintype "passive"))
      (node (ref "R17") (pin "1") (pinfunction "1_1") (pintype "passive"))
      (node (ref "R19") (pin "2") (pinfunction "2_2") (pintype "passive"))
      (node (ref "U5") (pin "T16") (pinfunction "SVREF_T16") (pintype "power_in"))
      (node (ref "U6") (pin "H1") (pinfunction "VREFDQ_H1") (pintype "passive"))
      (node (ref "U6") (pin "M8") (pinfunction "VREFCA_M8") (pintype "passive"))
    )
    (net (code "104") (name "/SWE") (class "Default")
      (node (ref "U5") (pin "W13") (pinfunction "SWE_W13") (pintype "output"))
      (node (ref "U6") (pin "L3") (pinfunction "#WE_L3") (pintype "passive"))
    )
    (net (code "105") (name "/UART0_RX") (class "Default")
      (node (ref "U5") (pin "H6") (pinfunction "PA5/UART0_RX/PWM0/PA_EINT5_H6") (pintype "passive"))
    )
    (net (code "106") (name "/UART0_TX") (class "Default")
      (node (ref "U5") (pin "F5") (pinfunction "PA4/UART0_TX/PA_EINT4_F5") (pintype "passive"))
    )
    (net (code "107") (name "/UART1_RX") (class "Default")
      (node (ref "U5") (pin "D3") (pinfunction "PG7/UART1_RX/PG_EINT7_D3") (pintype "passive"))
    )
    (net (code "108") (name "/UART1_TX") (class "Default")
      (node (ref "U5") (pin "G4") (pinfunction "PG6/UART1_TX/PG_EINT6_G4") (pintype "passive"))
    )
    (net (code "109") (name "/UART2_RX") (class "Default")
      (node (ref "U5") (pin "D5") (pinfunction "PA1/UART2_RX/JTAG_CK0/PA_EINT1_D5") (pintype "passive"))
    )
    (net (code "110") (name "/UART2_TX") (class "Default")
      (node (ref "U5") (pin "D11") (pinfunction "PA0/UART2_TX/JTAG_MS0/PA_EINT0_D11") (pintype "passive"))
    )
    (net (code "111") (name "/UART3_CTS") (class "Default")
      (node (ref "U5") (pin "D15") (pinfunction "PA16/SPI1_MISO/UART3_CTS/PA_EINT16_D15") (pintype "passive"))
    )
    (net (code "112") (name "/UART3_RTS") (class "Default")
      (node (ref "U5") (pin "F14") (pinfunction "PA15/SPI1_MOSI/UART3_RTS/PA_EINT15_F14") (pintype "passive"))
    )
    (net (code "113") (name "/UART3_RX") (class "Default")
      (node (ref "U5") (pin "G12") (pinfunction "PA14/SPI1_CLK/UART3_RX/PA_EINT14_G12") (pintype "passive"))
    )
    (net (code "114") (name "/UART3_TX") (class "Default")
      (node (ref "U5") (pin "E15") (pinfunction "PA13/SPI1_CS/UART3_TX/PA_EINT13_E15") (pintype "passive"))
    )
    (net (code "115") (name "/UBOOT") (class "Default")
      (node (ref "R22") (pin "1") (pinfunction "1_1") (pintype "passive"))
      (node (ref "U5") (pin "W6") (pinfunction "UBOOT_W6") (pintype "passive"))
    )
    (net (code "116") (name "/USB-DM0") (class "Default")
      (node (ref "U5") (pin "B5") (pinfunction "USB_DM0_B5") (pintype "passive"))
    )
    (net (code "117") (name "/USB-DM1") (class "Default")
      (node (ref "U5") (pin "B7") (pinfunction "USB_DM1_B7") (pintype "passive"))
    )
    (net (code "118") (name "/USB-DM2") (class "Default")
      (node (ref "U5") (pin "A8") (pinfunction "USB_DM2_A8") (pintype "passive"))
    )
    (net (code "119") (name "/USB-DM3") (class "Default")
      (node (ref "U5") (pin "B9") (pinfunction "USB_DM3_B9") (pintype "passive"))
    )
    (net (code "120") (name "/USB-DP0") (class "Default")
      (node (ref "U5") (pin "A5") (pinfunction "USB_DP0_A5") (pintype "passive"))
    )
    (net (code "121") (name "/USB-DP1") (class "Default")
      (node (ref "U5") (pin "B6") (pinfunction "USB_DP1_B6") (pintype "passive"))
    )
    (net (code "122") (name "/USB-DP2") (class "Default")
      (node (ref "U5") (pin "A7") (pinfunction "USB_DP2_A7") (pintype "passive"))
    )
    (net (code "123") (name "/USB-DP3") (class "Default")
      (node (ref "U5") (pin "B8") (pinfunction "USB_DP3_B8") (pintype "passive"))
    )
    (net (code "124") (name "/VDD_CPUFB") (class "Default")
      (node (ref "R26") (pin "1") (pinfunction "1_1") (pintype "passive"))
      (node (ref "U5") (pin "T10") (pinfunction "VDD_CPUFB_T10") (pintype "power_in"))
    )
    (net (code "125") (name "/XIN") (class "Default")
      (node (ref "C32") (pin "2") (pinfunction "2_2") (pintype "passive"))
      (node (ref "U5") (pin "K2") (pinfunction "X24MIN_K2") (pintype "passive"))
      (node (ref "Y1") (pin "1") (pinfunction "XIN_1") (pintype "passive"))
    )
    (net (code "126") (name "/XOUT") (class "Default")
      (node (ref "C31") (pin "1") (pinfunction "1_1") (pintype "passive"))
      (node (ref "U5") (pin "K1") (pinfunction "X24MOUT_K1") (pintype "output"))
      (node (ref "Y1") (pin "3") (pinfunction "XOUT_3") (pintype "passive"))
    )
    (net (code "127") (name "AGND") (class "Default")
      (node (ref "C43") (pin "2") (pinfunction "2_2") (pintype "passive"))
      (node (ref "C44") (pin "1") (pinfunction "1_1") (pintype "passive"))
      (node (ref "C45") (pin "1") (pinfunction "1_1") (pintype "passive"))
      (node (ref "C46") (pin "1") (pinfunction "1_1") (pintype "passive"))
      (node (ref "R25") (pin "1") (pinfunction "1_1") (pintype "passive"))
      (node (ref "U5") (pin "U3") (pinfunction "AGND_U3") (pintype "power_in"))
    )
    (net (code "128") (name "GND") (class "Default")
      (node (ref "C13") (pin "1") (pinfunction "1_1") (pintype "passive"))
      (node (ref "C14") (pin "1") (pinfunction "1_1") (pintype "passive"))
      (node (ref "C15") (pin "1") (pinfunction "1_1") (pintype "passive"))
      (node (ref "C16") (pin "1") (pinfunction "1_1") (pintype "passive"))
      (node (ref "C17") (pin "1") (pinfunction "1_1") (pintype "passive"))
      (node (ref "C18") (pin "1") (pinfunction "1_1") (pintype "passive"))
      (node (ref "C19") (pin "1") (pinfunction "1_1") (pintype "passive"))
      (node (ref "C20") (pin "1") (pinfunction "1_1") (pintype "passive"))
      (node (ref "C21") (pin "1") (pinfunction "1_1") (pintype "passive"))
      (node (ref "C22") (pin "1") (pinfunction "1_1") (pintype "passive"))
      (node (ref "C24") (pin "1") (pinfunction "1_1") (pintype "passive"))
      (node (ref "C25") (pin "1") (pinfunction "1_1") (pintype "passive"))
      (node (ref "C26") (pin "1") (pinfunction "1_1") (pintype "passive"))
      (node (ref "C27") (pin "1") (pinfunction "1_1") (pintype "passive"))
      (node (ref "C28") (pin "1") (pinfunction "1_1") (pintype "passive"))
      (node (ref "C29") (pin "1") (pinfunction "1_1") (pintype "passive"))
      (node (ref "C30") (pin "1") (pinfunction "1_1") (pintype "passive"))
      (node (ref "C31") (pin "2") (pinfunction "2_2") (pintype "passive"))
      (node (ref "C32") (pin "1") (pinfunction "1_1") (pintype "passive"))
      (node (ref "C33") (pin "2") (pinfunction "2_2") (pintype "passive"))
      (node (ref "C34") (pin "1") (pinfunction "1_1") (pintype "passive"))
      (node (ref "C35") (pin "1") (pinfunction "1_1") (pintype "passive"))
      (node (ref "C36") (pin "1") (pinfunction "1_1") (pintype "passive"))
      (node (ref "C37") (pin "2") (pinfunction "2_2") (pintype "passive"))
      (node (ref "C38") (pin "1") (pinfunction "1_1") (pintype "passive"))
      (node (ref "C39") (pin "1") (pinfunction "1_1") (pintype "passive"))
      (node (ref "C40") (pin "1") (pinfunction "1_1") (pintype "passive"))
      (node (ref "C41") (pin "1") (pinfunction "1_1") (pintype "passive"))
      (node (ref "C42") (pin "1") (pinfunction "1_1") (pintype "passive"))
      (node (ref "C47") (pin "1") (pinfunction "1_1") (pintype "passive"))
      (node (ref "C48") (pin "2") (pinfunction "2_2") (pintype "passive"))
      (node (ref "C52") (pin "1") (pinfunction "1_1") (pintype "passive"))
      (node (ref "C53") (pin "1") (pinfunction "1_1") (pintype "passive"))
      (node (ref "D1") (pin "2") (pinfunction "K_2") (pintype "passive"))
      (node (ref "D2") (pin "2") (pinfunction "K_2") (pintype "passive"))
      (node (ref "D3") (pin "2") (pinfunction "K_2") (pintype "passive"))
      (node (ref "R15") (pin "2") (pinfunction "2_2") (pintype "passive"))
      (node (ref "R16") (pin "2") (pinfunction "2_2") (pintype "passive"))
      (node (ref "R19") (pin "1") (pinfunction "1_1") (pintype "passive"))
      (node (ref "R20") (pin "2") (pinfunction "2_2") (pintype "passive"))
      (node (ref "R32") (pin "1") (pinfunction "1_1") (pintype "passive"))
      (node (ref "R33") (pin "1") (pinfunction "1_1") (pintype "passive"))
      (node (ref "U5") (pin "A20") (pinfunction "PD4/RGMII_RXCK/MII_RXCK/RMII_NULL_A20") (pintype "passive"))
      (node (ref "U5") (pin "A21") (pinfunction "GND_A21") (pintype "power_in"))
      (node (ref "U5") (pin "AA1") (pinfunction "GND_AA1") (pintype "power_in"))
      (node (ref "U5") (pin "B20") (pinfunction "PD2/RGMII_RXD1/MII_RXD1/RMII_RXD1_B20") (pintype "passive"))
      (node (ref "U5") (pin "B21") (pinfunction "PD6/RGMII_NULL/MII_RXERR/RMII_RXER_B21") (pintype "passive"))
      (node (ref "U5") (pin "C21") (pinfunction "PD0/RGMII_RXD3/MII_RXD3/RMII_NULL/DI_TX_C21") (pintype "passive"))
      (node (ref "U5") (pin "E18") (pinfunction "PD7/RGMII_TXD3/MII_TXD3/RMII_NULL_E18") (pintype "passive"))
      (node (ref "U5") (pin "E19") (pinfunction "PD12/RGMII_TXCK/MII_TXCK/RMII_TXCK_E19") (pintype "passive"))
      (node (ref "U5") (pin "E20") (pinfunction "PD8/RGMII_TXD2/MII_TXD2/RMII_NULL_E20") (pintype "passive"))
      (node (ref "U5") (pin "F19") (pinfunction "PD5/RGMII_RXCTL/MII_RXDV/RMII_CRS_DV_F19") (pintype "passive"))
      (node (ref "U5") (pin "F20") (pinfunction "PD11/RGMII_NULL/MII_CRS/RMII_NULL_F20") (pintype "passive"))
      (node (ref "U5") (pin "F21") (pinfunction "PD9/RGMII_TXD1/MII_TXD1/RMII_TXD1_F21") (pintype "passive"))
      (node (ref "U5") (pin "G8") (pinfunction "GND_G8") (pintype "power_in"))
      (node (ref "U5") (pin "H12") (pinfunction "GND_H12") (pintype "power_in"))
      (node (ref "U5") (pin "H15") (pinfunction "GND_H15") (pintype "power_in"))
      (node (ref "U5") (pin "H17") (pinfunction "PD1/RGMII_RXD2/MII_RXD2/RMII_NULL/DI_RX_H17") (pintype "passive"))
      (node (ref "U5") (pin "H18") (pinfunction "PD3/RGMII_RXD0/MII_RXD0/RMII_RXD0_H18") (pintype "passive"))
      (node (ref "U5") (pin "H19") (pinfunction "PD10/RGMII_TXD0/MII_TXD0/RMII_TXD0_H19") (pintype "passive"))
      (node (ref "U5") (pin "H8") (pinfunction "GND_TV_H8") (pintype "power_in"))
      (node (ref "U5") (pin "J13") (pinfunction "GND_J13") (pintype "power_in"))
      (node (ref "U5") (pin "J16") (pinfunction "GND_J16") (pintype "power_in"))
      (node (ref "U5") (pin "J9") (pinfunction "GND_J9") (pintype "power_in"))
      (node (ref "U5") (pin "K13") (pinfunction "GND_K13") (pintype "power_in"))
      (node (ref "U5") (pin "K14") (pinfunction "GND_K14") (pintype "power_in"))
      (node (ref "U5") (pin "K15") (pinfunction "GND_K15") (pintype "power_in"))
      (node (ref "U5") (pin "K16") (pinfunction "GND_K16") (pintype "power_in"))
      (node (ref "U5") (pin "K17") (pinfunction "PD13/RGMII_TXCTL/MII_TXEN/RMII_TXEN_K17") (pintype "passive"))
      (node (ref "U5") (pin "K18") (pinfunction "PD15/RGMII_CLKIN/MII_COL/RMII_NULL_K18") (pintype "passive"))
      (node (ref "U5") (pin "K7") (pinfunction "GND_K7") (pintype "power_in"))
      (node (ref "U5") (pin "K8") (pinfunction "GND_K8") (pintype "power_in"))
      (node (ref "U5") (pin "K9") (pinfunction "GND_K9") (pintype "power_in"))
      (node (ref "U5") (pin "L15") (pinfunction "GND_L15") (pintype "power_in"))
      (node (ref "U5") (pin "L17") (pinfunction "PD14/RGMII_NULL/MII_TXERR/RMII_NULL_L17") (pintype "passive"))
      (node (ref "U5") (pin "L18") (pinfunction "PD16/MDC_L18") (pintype "passive"))
      (node (ref "U5") (pin "L19") (pinfunction "PD17/MDIO_L19") (pintype "passive"))
      (node (ref "U5") (pin "L8") (pinfunction "GND_L8") (pintype "power_in"))
      (node (ref "U5") (pin "L9") (pinfunction "GND_L9") (pintype "power_in"))
      (node (ref "U5") (pin "M10") (pinfunction "GND_M10") (pintype "power_in"))
      (node (ref "U5") (pin "M11") (pinfunction "GND_M11") (pintype "power_in"))
      (node (ref "U5") (pin "M12") (pinfunction "GND_M12") (pintype "power_in"))
      (node (ref "U5") (pin "M13") (pinfunction "GND_M13") (pintype "power_in"))
      (node (ref "U5") (pin "M14") (pinfunction "GND_M14") (pintype "power_in"))
      (node (ref "U5") (pin "M15") (pinfunction "GND_M15") (pintype "power_in"))
      (node (ref "U5") (pin "M5") (pinfunction "HGND_M5") (pintype "power_in"))
      (node (ref "U5") (pin "M7") (pinfunction "GND_M7") (pintype "power_in"))
      (node (ref "U5") (pin "M8") (pinfunction "GND_M8") (pintype "power_in"))
      (node (ref "U5") (pin "M9") (pinfunction "GND_M9") (pintype "power_in"))
      (node (ref "U5") (pin "N10") (pinfunction "GND_N10") (pintype "power_in"))
      (node (ref "U5") (pin "N11") (pinfunction "GND_N11") (pintype "power_in"))
      (node (ref "U5") (pin "N12") (pinfunction "GND_N12") (pintype "power_in"))
      (node (ref "U5") (pin "N13") (pinfunction "GND_N13") (pintype "power_in"))
      (node (ref "U5") (pin "N14") (pinfunction "GND_N14") (pintype "power_in"))
      (node (ref "U5") (pin "N15") (pinfunction "GND_N15") (pintype "power_in"))
      (node (ref "U5") (pin "N7") (pinfunction "GND_N7") (pintype "power_in"))
      (node (ref "U5") (pin "N9") (pinfunction "GND_N9") (pintype "power_in"))
      (node (ref "U5") (pin "P10") (pinfunction "GND_P10") (pintype "power_in"))
      (node (ref "U5") (pin "P11") (pinfunction "GND_P11") (pintype "power_in"))
      (node (ref "U5") (pin "P12") (pinfunction "GND_P12") (pintype "power_in"))
      (node (ref "U5") (pin "P13") (pinfunction "GND_P13") (pintype "power_in"))
      (node (ref "U5") (pin "P14") (pinfunction "GND_P14") (pintype "power_in"))
      (node (ref "U5") (pin "P15") (pinfunction "GND_P15") (pintype "power_in"))
      (node (ref "U5") (pin "R10") (pinfunction "GND_R10") (pintype "power_in"))
      (node (ref "U5") (pin "R11") (pinfunction "GND_R11") (pintype "power_in"))
      (node (ref "U5") (pin "R12") (pinfunction "GND_R12") (pintype "power_in"))
      (node (ref "U5") (pin "R13") (pinfunction "GND_R13") (pintype "power_in"))
      (node (ref "U5") (pin "R14") (pinfunction "GND_R14") (pintype "power_in"))
      (node (ref "U5") (pin "R9") (pinfunction "GND_R9") (pintype "power_in"))
      (node (ref "U5") (pin "T11") (pinfunction "GND_T11") (pintype "power_in"))
      (node (ref "U5") (pin "T9") (pinfunction "GND_CPUXFB_T9") (pintype "power_in"))
      (node (ref "U6") (pin "A9") (pinfunction "VSS_A9") (pintype "passive"))
      (node (ref "U6") (pin "B1") (pinfunction "VSSQ_B1") (pintype "passive"))
      (node (ref "U6") (pin "B3") (pinfunction "VSS_B3") (pintype "passive"))
      (node (ref "U6") (pin "B9") (pinfunction "VSSQ_B9") (pintype "passive"))
      (node (ref "U6") (pin "D1") (pinfunction "VSSQ_D1") (pintype "passive"))
      (node (ref "U6") (pin "D8") (pinfunction "VSSQ_D8") (pintype "passive"))
      (node (ref "U6") (pin "E1") (pinfunction "VSS_E1") (pintype "passive"))
      (node (ref "U6") (pin "E2") (pinfunction "VSSQ_E2") (pintype "passive"))
      (node (ref "U6") (pin "E8") (pinfunction "VSSQ_E8") (pintype "passive"))
      (node (ref "U6") (pin "F9") (pinfunction "VSSQ_F9") (pintype "passive"))
      (node (ref "U6") (pin "G1") (pinfunction "VSSQ_G1") (pintype "passive"))
      (node (ref "U6") (pin "G8") (pinfunction "VSS_G8") (pintype "passive"))
      (node (ref "U6") (pin "G9") (pinfunction "VSSQ_G9") (pintype "passive"))
      (node (ref "U6") (pin "J2") (pinfunction "VSS_J2") (pintype "passive"))
      (node (ref "U6") (pin "J8") (pinfunction "VSS_J8") (pintype "passive"))
      (node (ref "U6") (pin "M1") (pinfunction "VSS_M1") (pintype "passive"))
      (node (ref "U6") (pin "M9") (pinfunction "VSS_M9") (pintype "passive"))
      (node (ref "U6") (pin "P1") (pinfunction "VSS_P1") (pintype "passive"))
      (node (ref "U6") (pin "P9") (pinfunction "VSS_P9") (pintype "passive"))
      (node (ref "U6") (pin "T1") (pinfunction "VSS_T1") (pintype "passive"))
      (node (ref "U6") (pin "T9") (pinfunction "VSS_T9") (pintype "passive"))
      (node (ref "Y1") (pin "2") (pinfunction "GND_2") (pintype "passive"))
      (node (ref "Y1") (pin "4") (pinfunction "GND_4") (pintype "passive"))
    )
    (net (code "129") (name "Net-(C50-Pad1)") (class "Default")
      (node (ref "C50") (pin "1") (pinfunction "1_1") (pintype "passive"))
      (node (ref "R31") (pin "1") (pinfunction "1_1") (pintype "passive"))
      (node (ref "R32") (pin "2") (pinfunction "2_2") (pintype "passive"))
    )
    (net (code "130") (name "Net-(C50-Pad2)") (class "Default")
      (node (ref "C50") (pin "2") (pinfunction "2_2") (pintype "passive"))
      (node (ref "R29") (pin "1") (pinfunction "1_1") (pintype "passive"))
      (node (ref "R30") (pin "2") (pinfunction "2_2") (pintype "passive"))
    )
    (net (code "131") (name "Net-(D1-A)") (class "Default")
      (node (ref "D1") (pin "1") (pinfunction "A_1") (pintype "passive"))
      (node (ref "R36") (pin "2") (pinfunction "2_2") (pintype "passive"))
    )
    (net (code "132") (name "Net-(D2-A)") (class "Default")
      (node (ref "D2") (pin "1") (pinfunction "A_1") (pintype "passive"))
      (node (ref "R37") (pin "2") (pinfunction "2_2") (pintype "passive"))
    )
    (net (code "133") (name "Net-(D3-A)") (class "Default")
      (node (ref "D3") (pin "1") (pinfunction "A_1") (pintype "passive"))
      (node (ref "R38") (pin "2") (pinfunction "2_2") (pintype "passive"))
    )
    (net (code "134") (name "Net-(R16-Pad1)") (class "Default")
      (node (ref "R16") (pin "1") (pinfunction "1_1") (pintype "passive"))
      (node (ref "U6") (pin "L9") (pinfunction "NC_L9") (pintype "passive"))
    )
    (net (code "135") (name "Net-(U5-EPHY_RTX)") (class "Default")
      (node (ref "R33") (pin "2") (pinfunction "2_2") (pintype "passive"))
      (node (ref "U5") (pin "F6") (pinfunction "EPHY_RTX_F6") (pintype "passive"))
    )
    (net (code "136") (name "Net-(U5-NMI)") (class "Default")
      (node (ref "R28") (pin "2") (pinfunction "2_2") (pintype "passive"))
      (node (ref "U5") (pin "AA6") (pinfunction "NMI_AA6") (pintype "passive"))
    )
    (net (code "137") (name "Net-(U5-SZQ)") (class "Default")
      (node (ref "R20") (pin "1") (pinfunction "1_1") (pintype "passive"))
      (node (ref "U5") (pin "V10") (pinfunction "SZQ_V10") (pintype "passive"))
    )
    (net (code "138") (name "Net-(U5-VDD_EFUSEBP)") (class "Default")
      (node (ref "C33") (pin "1") (pinfunction "1_1") (pintype "passive"))
      (node (ref "U5") (pin "H11") (pinfunction "VDD_EFUSEBP_H11") (pintype "power_in"))
    )
    (net (code "139") (name "Net-(U5-VRA1)") (class "Default")
      (node (ref "C43") (pin "1") (pinfunction "1_1") (pintype "passive"))
      (node (ref "U5") (pin "Y4") (pinfunction "VRA1_Y4") (pintype "passive"))
    )
    (net (code "140") (name "Net-(U5-VRA2)") (class "Default")
      (node (ref "C44") (pin "2") (pinfunction "2_2") (pintype "passive"))
      (node (ref "R25") (pin "2") (pinfunction "2_2") (pintype "passive"))
      (node (ref "U5") (pin "W5") (pinfunction "VRA2_W5") (pintype "passive"))
    )
    (net (code "141") (name "Net-(U5-VRP)") (class "Default")
      (node (ref "C45") (pin "2") (pinfunction "2_2") (pintype "passive"))
      (node (ref "C46") (pin "2") (pinfunction "2_2") (pintype "passive"))
      (node (ref "U5") (pin "V4") (pinfunction "VRP_V4") (pintype "passive"))
    )
    (net (code "142") (name "Net-(U6-ZQ)") (class "Default")
      (node (ref "R15") (pin "1") (pinfunction "1_1") (pintype "passive"))
      (node (ref "U6") (pin "L8") (pinfunction "ZQ_L8") (pintype "passive"))
    )
    (net (code "143") (name "VCC-DRAM") (class "Default")
      (node (ref "C13") (pin "2") (pinfunction "2_2") (pintype "passive"))
      (node (ref "C14") (pin "2") (pinfunction "2_2") (pintype "passive"))
      (node (ref "C15") (pin "2") (pinfunction "2_2") (pintype "passive"))
      (node (ref "C16") (pin "2") (pinfunction "2_2") (pintype "passive"))
      (node (ref "C17") (pin "2") (pinfunction "2_2") (pintype "passive"))
      (node (ref "C18") (pin "2") (pinfunction "2_2") (pintype "passive"))
      (node (ref "C19") (pin "2") (pinfunction "2_2") (pintype "passive"))
      (node (ref "C20") (pin "2") (pinfunction "2_2") (pintype "passive"))
      (node (ref "C23") (pin "2") (pinfunction "2_2") (pintype "passive"))
      (node (ref "R17") (pin "2") (pinfunction "2_2") (pintype "passive"))
      (node (ref "U5") (pin "L16") (pinfunction "VCC-DRAM_L16") (pintype "power_in"))
      (node (ref "U5") (pin "M16") (pinfunction "VCC-DRAM_M16") (pintype "power_in"))
      (node (ref "U5") (pin "N16") (pinfunction "VCC-DRAM_N16") (pintype "power_in"))
      (node (ref "U5") (pin "P16") (pinfunction "VCC-DRAM_P16") (pintype "power_in"))
      (node (ref "U5") (pin "P17") (pinfunction "VCC-DRAM_P17") (pintype "power_in"))
      (node (ref "U5") (pin "R16") (pinfunction "VCC-DRAM_R16") (pintype "power_in"))
      (node (ref "U5") (pin "T12") (pinfunction "VCC-DRAM_T12") (pintype "power_in"))
      (node (ref "U5") (pin "T13") (pinfunction "VCC-DRAM_T13") (pintype "power_in"))
      (node (ref "U5") (pin "T14") (pinfunction "VCC-DRAM_T14") (pintype "power_in"))
      (node (ref "U5") (pin "T15") (pinfunction "VCC-DRAM_T15") (pintype "power_in"))
      (node (ref "U5") (pin "U11") (pinfunction "VCC-DRAM_U11") (pintype "power_in"))
      (node (ref "U6") (pin "A1") (pinfunction "VDDQ_A1") (pintype "passive"))
      (node (ref "U6") (pin "A8") (pinfunction "VDDQ_A8") (pintype "passive"))
      (node (ref "U6") (pin "B2") (pinfunction "VDD_B2") (pintype "passive"))
      (node (ref "U6") (pin "C1") (pinfunction "VDDQ_C1") (pintype "passive"))
      (node (ref "U6") (pin "C9") (pinfunction "VDDQ_C9") (pintype "passive"))
      (node (ref "U6") (pin "D2") (pinfunction "VDDQ_D2") (pintype "passive"))
      (node (ref "U6") (pin "D9") (pinfunction "VDD_D9") (pintype "passive"))
      (node (ref "U6") (pin "E9") (pinfunction "VDDQ_E9") (pintype "passive"))
      (node (ref "U6") (pin "F1") (pinfunction "VDDQ_F1") (pintype "passive"))
      (node (ref "U6") (pin "G7") (pinfunction "VDD_G7") (pintype "passive"))
      (node (ref "U6") (pin "H2") (pinfunction "VDDQ_H2") (pintype "passive"))
      (node (ref "U6") (pin "H9") (pinfunction "VDDQ_H9") (pintype "passive"))
      (node (ref "U6") (pin "K2") (pinfunction "VDD_K2") (pintype "passive"))
      (node (ref "U6") (pin "K8") (pinfunction "VDD_K8") (pintype "passive"))
      (node (ref "U6") (pin "N1") (pinfunction "VDD_N1") (pintype "passive"))
      (node (ref "U6") (pin "N9") (pinfunction "VDD_N9") (pintype "passive"))
      (node (ref "U6") (pin "R1") (pinfunction "VDD_R1") (pintype "passive"))
      (node (ref "U6") (pin "R9") (pinfunction "VDD_R9") (pintype "passive"))
    )
    (net (code "144") (name "VDD-CPUS") (class "Default")
      (node (ref "C29") (pin "2") (pinfunction "2_2") (pintype "passive"))
      (node (ref "C30") (pin "2") (pinfunction "2_2") (pintype "passive"))
      (node (ref "U5") (pin "J7") (pinfunction "VDD_CPUS_J7") (pintype "power_in"))
      (node (ref "U5") (pin "J8") (pinfunction "VDD_CPUS_J8") (pintype "power_in"))
      (node (ref "U5") (pin "M4") (pinfunction "RTC_VIO_M4") (pintype "power_in"))
    )
    (net (code "145") (name "VDD-CPUX") (class "Default")
      (node (ref "C39") (pin "2") (pinfunction "2_2") (pintype "passive"))
      (node (ref "C40") (pin "2") (pinfunction "2_2") (pintype "passive"))
      (node (ref "C41") (pin "2") (pinfunction "2_2") (pintype "passive"))
      (node (ref "R26") (pin "2") (pinfunction "2_2") (pintype "passive"))
      (node (ref "U5") (pin "N8") (pinfunction "VDD_CPUX_N8") (pintype "power_in"))
      (node (ref "U5") (pin "P6") (pinfunction "VDD_CPUX_P6") (pintype "power_in"))
      (node (ref "U5") (pin "P7") (pinfunction "VDD_CPUX_P7") (pintype "power_in"))
      (node (ref "U5") (pin "P8") (pinfunction "VDD_CPUX_P8") (pintype "power_in"))
      (node (ref "U5") (pin "P9") (pinfunction "VDD_CPUX_P9") (pintype "power_in"))
      (node (ref "U5") (pin "R6") (pinfunction "VDD_CPUX_R6") (pintype "power_in"))
      (node (ref "U5") (pin "R7") (pinfunction "VDD_CPUX_R7") (pintype "power_in"))
      (node (ref "U5") (pin "R8") (pinfunction "VDD_CPUX_R8") (pintype "power_in"))
      (node (ref "U5") (pin "T6") (pinfunction "VDD_CPUX_T6") (pintype "power_in"))
      (node (ref "U5") (pin "T7") (pinfunction "VDD_CPUX_T7") (pintype "power_in"))
      (node (ref "U5") (pin "T8") (pinfunction "VDD_CPUX_T8") (pintype "power_in"))
      (node (ref "U5") (pin "U6") (pinfunction "VDD_CPUX_U6") (pintype "power_in"))
      (node (ref "U5") (pin "U9") (pinfunction "VDD_CPUX_U9") (pintype "power_in"))
    )
    (net (code "146") (name "VDD1V1-EPHY") (class "Default")
      (node (ref "C38") (pin "2") (pinfunction "2_2") (pintype "passive"))
      (node (ref "U5") (pin "F8") (pinfunction "EPHY_VDD_F8") (pintype "power_in"))
    )
    (net (code "147") (name "VDD1V2-SYS") (class "Default")
      (node (ref "C34") (pin "2") (pinfunction "2_2") (pintype "passive"))
      (node (ref "C35") (pin "2") (pinfunction "2_2") (pintype "passive"))
      (node (ref "C36") (pin "2") (pinfunction "2_2") (pintype "passive"))
      (node (ref "U5") (pin "H10") (pinfunction "VDD_SYS_H10") (pintype "power_in"))
      (node (ref "U5") (pin "J10") (pinfunction "VDD_SYS_J10") (pintype "power_in"))
      (node (ref "U5") (pin "J11") (pinfunction "VDD_SYS_J11") (pintype "power_in"))
      (node (ref "U5") (pin "J12") (pinfunction "VDD_SYS_J12") (pintype "power_in"))
      (node (ref "U5") (pin "K10") (pinfunction "VDD_SYS_K10") (pintype "power_in"))
      (node (ref "U5") (pin "K11") (pinfunction "VDD_SYS_K11") (pintype "power_in"))
      (node (ref "U5") (pin "K12") (pinfunction "VDD_SYS_K12") (pintype "power_in"))
      (node (ref "U5") (pin "L10") (pinfunction "VDD_SYS_L10") (pintype "power_in"))
      (node (ref "U5") (pin "L11") (pinfunction "VDD_SYS_L11") (pintype "power_in"))
      (node (ref "U5") (pin "L12") (pinfunction "VDD_SYS_L12") (pintype "power_in"))
      (node (ref "U5") (pin "L13") (pinfunction "VDD_SYS_L13") (pintype "power_in"))
      (node (ref "U5") (pin "L14") (pinfunction "VDD_SYS_L14") (pintype "power_in"))
    )
    (net (code "148") (name "VDD_AV_3.3V") (class "Default")
      (node (ref "C37") (pin "1") (pinfunction "1_1") (pintype "passive"))
      (node (ref "C42") (pin "2") (pinfunction "2_2") (pintype "passive"))
      (node (ref "R21") (pin "2") (pinfunction "2_2") (pintype "passive"))
      (node (ref "R22") (pin "2") (pinfunction "2_2") (pintype "passive"))
      (node (ref "R23") (pin "2") (pinfunction "2_2") (pintype "passive"))
      (node (ref "R24") (pin "2") (pinfunction "2_2") (pintype "passive"))
      (node (ref "R27") (pin "1") (pinfunction "1_1") (pintype "passive"))
      (node (ref "R28") (pin "1") (pinfunction "1_1") (pintype "passive"))
      (node (ref "U5") (pin "G9") (pinfunction "V33_TV_G9") (pintype "power_in"))
      (node (ref "U5") (pin "K6") (pinfunction "VCC_RTC_K6") (pintype "power_in"))
      (node (ref "U5") (pin "N3") (pinfunction "VCC_PLL_N3") (pintype "power_in"))
      (node (ref "U5") (pin "V3") (pinfunction "AVCC_V3") (pintype "power_in"))
    )
    (net (code "149") (name "VDD_SYS_3.3V") (class "Default")
      (node (ref "C25") (pin "2") (pinfunction "2_2") (pintype "passive"))
      (node (ref "C26") (pin "2") (pinfunction "2_2") (pintype "passive"))
      (node (ref "C27") (pin "2") (pinfunction "2_2") (pintype "passive"))
      (node (ref "C28") (pin "2") (pinfunction "2_2") (pintype "passive"))
      (node (ref "U5") (pin "G10") (pinfunction "VDD_EFUSE_G10") (pintype "power_in"))
      (node (ref "U5") (pin "G11") (pinfunction "VCC_USB_G11") (pintype "power_in"))
      (node (ref "U5") (pin "G13") (pinfunction "VCC_IO_G13") (pintype "power_in"))
      (node (ref "U5") (pin "G14") (pinfunction "VCC_IO_G14") (pintype "power_in"))
      (node (ref "U5") (pin "G15") (pinfunction "VCC_IO_G15") (pintype "power_in"))
      (node (ref "U5") (pin "G7") (pinfunction "EPHY_VCC_G7") (pintype "power_in"))
      (node (ref "U5") (pin "H13") (pinfunction "VCC_IO_H13") (pintype "power_in"))
      (node (ref "U5") (pin "H14") (pinfunction "VCC_IO_H14") (pintype "power_in"))
      (node (ref "U5") (pin "H7") (pinfunction "VCC_PG_H7") (pintype "power_in"))
      (node (ref "U5") (pin "J14") (pinfunction "VCC_IO_J14") (pintype "power_in"))
      (node (ref "U5") (pin "J15") (pinfunction "VCC_PD_J15") (pintype "power_in"))
      (node (ref "U5") (pin "J6") (pinfunction "HVCC_J6") (pintype "power_in"))
    )
    (net (code "150") (name "unconnected-(U5-HCEC-PadG5)") (class "Default")
      (node (ref "U5") (pin "G5") (pinfunction "HCEC_G5") (pintype "passive+no_connect"))
    )
    (net (code "151") (name "unconnected-(U5-HHPD-PadM2)") (class "Default")
      (node (ref "U5") (pin "M2") (pinfunction "HHPD_M2") (pintype "passive+no_connect"))
    )
    (net (code "152") (name "unconnected-(U5-HSCL-PadH3)") (class "Default")
      (node (ref "U5") (pin "H3") (pinfunction "HSCL_H3") (pintype "output+no_connect"))
    )
    (net (code "153") (name "unconnected-(U5-HSDA-PadK3)") (class "Default")
      (node (ref "U5") (pin "K3") (pinfunction "HSDA_K3") (pintype "passive+no_connect"))
    )
    (net (code "154") (name "unconnected-(U5-HTX0N-PadF1)") (class "Default")
      (node (ref "U5") (pin "F1") (pinfunction "HTX0N_F1") (pintype "output+no_connect"))
    )
    (net (code "155") (name "unconnected-(U5-HTX0P-PadG1)") (class "Default")
      (node (ref "U5") (pin "G1") (pinfunction "HTX0P_G1") (pintype "output+no_connect"))
    )
    (net (code "156") (name "unconnected-(U5-HTX1N-PadG2)") (class "Default")
      (node (ref "U5") (pin "G2") (pinfunction "HTX1N_G2") (pintype "output+no_connect"))
    )
    (net (code "157") (name "unconnected-(U5-HTX1P-PadH2)") (class "Default")
      (node (ref "U5") (pin "H2") (pinfunction "HTX1P_H2") (pintype "output+no_connect"))
    )
    (net (code "158") (name "unconnected-(U5-HTX2N-PadJ2)") (class "Default")
      (node (ref "U5") (pin "J2") (pinfunction "HTX2N_J2") (pintype "output+no_connect"))
    )
    (net (code "159") (name "unconnected-(U5-HTX2P-PadJ1)") (class "Default")
      (node (ref "U5") (pin "J1") (pinfunction "HTX2P_J1") (pintype "output+no_connect"))
    )
    (net (code "160") (name "unconnected-(U5-HTXCN-PadE2)") (class "Default")
      (node (ref "U5") (pin "E2") (pinfunction "HTXCN_E2") (pintype "output+no_connect"))
    )
    (net (code "161") (name "unconnected-(U5-HTXCP-PadF2)") (class "Default")
      (node (ref "U5") (pin "F2") (pinfunction "HTXCP_F2") (pintype "output+no_connect"))
    )
    (net (code "162") (name "unconnected-(U5-JTAG-SEL0-PadA1)") (class "Default")
      (node (ref "U5") (pin "A1") (pinfunction "JTAG-SEL0_A1") (pintype "passive+no_connect"))
    )
    (net (code "163") (name "unconnected-(U5-JTAG-SEL1-PadB2)") (class "Default")
      (node (ref "U5") (pin "B2") (pinfunction "JTAG-SEL1_B2") (pintype "passive+no_connect"))
    )
    (net (code "164") (name "unconnected-(U5-LINEINL-PadV1)") (class "Default")
      (node (ref "U5") (pin "V1") (pinfunction "LINEINL_V1") (pintype "passive+no_connect"))
    )
    (net (code "165") (name "unconnected-(U5-LINEINR-PadW1)") (class "Default")
      (node (ref "U5") (pin "W1") (pinfunction "LINEINR_W1") (pintype "passive+no_connect"))
    )
    (net (code "166") (name "unconnected-(U5-MICIN2N-PadAA2)") (class "Default")
      (node (ref "U5") (pin "AA2") (pinfunction "MICIN2N_AA2") (pintype "passive+no_connect"))
    )
    (net (code "167") (name "unconnected-(U5-MICIN2P-PadY2)") (class "Default")
      (node (ref "U5") (pin "Y2") (pinfunction "MICIN2P_Y2") (pintype "passive+no_connect"))
    )
    (net (code "168") (name "unconnected-(U5-NC-PadK4)") (class "Default")
      (node (ref "U5") (pin "K4") (pinfunction "NC_K4") (pintype "passive+no_connect"))
    )
    (net (code "169") (name "unconnected-(U5-PA2{slash}UART2_RTS{slash}JTAG_DO0{slash}PA_EINT2-PadD6)") (class "Default")
      (node (ref "U5") (pin "D6") (pinfunction "PA2/UART2_RTS/JTAG_DO0/PA_EINT2_D6") (pintype "passive+no_connect"))
    )
    (net (code "170") (name "unconnected-(U5-PA3{slash}UART2_CTS{slash}JTAG_DI0{slash}PA_EINT3-PadE13)") (class "Default")
      (node (ref "U5") (pin "E13") (pinfunction "PA3/UART2_CTS/JTAG_DI0/PA_EINT3_E13") (pintype "passive+no_connect"))
    )
    (net (code "171") (name "unconnected-(U5-PA6{slash}SIM_PWREN{slash}PWM1{slash}PA_EINT6-PadE14)") (class "Default")
      (node (ref "U5") (pin "E14") (pinfunction "PA6/SIM_PWREN/PWM1/PA_EINT6_E14") (pintype "passive+no_connect"))
    )
    (net (code "172") (name "unconnected-(U5-PA7{slash}SIM_CLK{slash}PA_EINT7-PadD8)") (class "Default")
      (node (ref "U5") (pin "D8") (pinfunction "PA7/SIM_CLK/PA_EINT7_D8") (pintype "passive+no_connect"))
    )
    (net (code "173") (name "unconnected-(U5-PA8{slash}SIM_DATA{slash}PA_EINT8-PadF13)") (class "Default")
      (node (ref "U5") (pin "F13") (pinfunction "PA8/SIM_DATA/PA_EINT8_F13") (pintype "passive+no_connect"))
    )
    (net (code "174") (name "unconnected-(U5-PA9{slash}SIM_RST{slash}PA_EINT9-PadD13)") (class "Default")
      (node (ref "U5") (pin "D13") (pinfunction "PA9/SIM_RST/PA_EINT9_D13") (pintype "passive+no_connect"))
    )
    (net (code "175") (name "unconnected-(U5-PA17{slash}SPDIF_OUT(OWA_OUT){slash}PA_EINT17-PadC14)") (class "Default")
      (node (ref "U5") (pin "C14") (pinfunction "PA17/SPDIF_OUT(OWA_OUT)/PA_EINT17_C14") (pintype "passive+no_connect"))
    )
    (net (code "176") (name "unconnected-(U5-PA20{slash}PCM0_DOUT{slash}SIM_VPPEN{slash}PA_EINT20-PadA13)") (class "Default")
      (node (ref "U5") (pin "A13") (pinfunction "PA20/PCM0_DOUT/SIM_VPPEN/PA_EINT20_A13") (pintype "passive+no_connect"))
    )
    (net (code "177") (name "unconnected-(U5-PA21{slash}PCM0_DIN{slash}SIM_VPPPP{slash}PA_EINT21-PadA14)") (class "Default")
      (node (ref "U5") (pin "A14") (pinfunction "PA21/PCM0_DIN/SIM_VPPPP/PA_EINT21_A14") (pintype "passive+no_connect"))
    )
    (net (code "178") (name "unconnected-(U5-PC4{slash}NAND_CE0-PadF16)") (class "Default")
      (node (ref "U5") (pin "F16") (pinfunction "PC4/NAND_CE0_F16") (pintype "passive+no_connect"))
    )
    (net (code "179") (name "unconnected-(U5-PC7{slash}NAND_RB1-PadA16)") (class "Default")
      (node (ref "U5") (pin "A16") (pinfunction "PC7/NAND_RB1_A16") (pintype "passive+no_connect"))
    )
    (net (code "180") (name "unconnected-(U5-PE0{slash}CSI_PCLK{slash}TS_CLK-PadB10)") (class "Default")
      (node (ref "U5") (pin "B10") (pinfunction "PE0/CSI_PCLK/TS_CLK_B10") (pintype "passive+no_connect"))
    )
    (net (code "181") (name "unconnected-(U5-PE1{slash}CSI_MCLK{slash}TS_ERR-PadA10)") (class "Default")
      (node (ref "U5") (pin "A10") (pinfunction "PE1/CSI_MCLK/TS_ERR_A10") (pintype "passive+no_connect"))
    )
    (net (code "182") (name "unconnected-(U5-PE2{slash}CSI_HSYNC{slash}TS_SYNC-PadB11)") (class "Default")
      (node (ref "U5") (pin "B11") (pinfunction "PE2/CSI_HSYNC/TS_SYNC_B11") (pintype "passive+no_connect"))
    )
    (net (code "183") (name "unconnected-(U5-PE3{slash}CSI_VSYNC{slash}TS_DVLD-PadC10)") (class "Default")
      (node (ref "U5") (pin "C10") (pinfunction "PE3/CSI_VSYNC/TS_DVLD_C10") (pintype "passive+no_connect"))
    )
    (net (code "184") (name "unconnected-(U5-PE4{slash}CSI_D0{slash}TS_D0-PadC9)") (class "Default")
      (node (ref "U5") (pin "C9") (pinfunction "PE4/CSI_D0/TS_D0_C9") (pintype "passive+no_connect"))
    )
    (net (code "185") (name "unconnected-(U5-PE5{slash}CSI_D1{slash}TS_D1-PadE10)") (class "Default")
      (node (ref "U5") (pin "E10") (pinfunction "PE5/CSI_D1/TS_D1_E10") (pintype "passive+no_connect"))
    )
    (net (code "186") (name "unconnected-(U5-PE6{slash}CSI_D2{slash}TS_D2-PadD10)") (class "Default")
      (node (ref "U5") (pin "D10") (pinfunction "PE6/CSI_D2/TS_D2_D10") (pintype "passive+no_connect"))
    )
    (net (code "187") (name "unconnected-(U5-PE7{slash}CSI_D3{slash}TS_D3-PadC8)") (class "Default")
      (node (ref "U5") (pin "C8") (pinfunction "PE7/CSI_D3/TS_D3_C8") (pintype "passive+no_connect"))
    )
    (net (code "188") (name "unconnected-(U5-PE8{slash}CSI_D4{slash}TS_D4-PadC11)") (class "Default")
      (node (ref "U5") (pin "C11") (pinfunction "PE8/CSI_D4/TS_D4_C11") (pintype "passive+no_connect"))
    )
    (net (code "189") (name "unconnected-(U5-PE9{slash}CSI_D5{slash}TS_D5-PadC12)") (class "Default")
      (node (ref "U5") (pin "C12") (pinfunction "PE9/CSI_D5/TS_D5_C12") (pintype "passive+no_connect"))
    )
    (net (code "190") (name "unconnected-(U5-PE10{slash}CSI_D6{slash}TS_D6-PadE8)") (class "Default")
      (node (ref "U5") (pin "E8") (pinfunction "PE10/CSI_D6/TS_D6_E8") (pintype "passive+no_connect"))
    )
    (net (code "191") (name "unconnected-(U5-PE11{slash}CSI_D7{slash}TS_D7-PadA11)") (class "Default")
      (node (ref "U5") (pin "A11") (pinfunction "PE11/CSI_D7/TS_D7_A11") (pintype "passive+no_connect"))
    )
    (net (code "192") (name "unconnected-(U5-PE12{slash}CSI_SCK{slash}TWI2_SCK-PadB12)") (class "Default")
      (node (ref "U5") (pin "B12") (pinfunction "PE12/CSI_SCK/TWI2_SCK_B12") (pintype "passive+no_connect"))
    )
    (net (code "193") (name "unconnected-(U5-PE13{slash}CSI_SDA{slash}TWI2_SDA-PadC7)") (class "Default")
      (node (ref "U5") (pin "C7") (pinfunction "PE13/CSI_SDA/TWI2_SDA_C7") (pintype "passive+no_connect"))
    )
    (net (code "194") (name "unconnected-(U5-PE14-PadC6)") (class "Default")
      (node (ref "U5") (pin "C6") (pinfunction "PE14_C6") (pintype "passive+no_connect"))
    )
    (net (code "195") (name "unconnected-(U5-PE15-PadC5)") (class "Default")
      (node (ref "U5") (pin "C5") (pinfunction "PE15_C5") (pintype "passive+no_connect"))
    )
    (net (code "196") (name "unconnected-(U5-PG0{slash}SDC1_CLK{slash}PG_EINT0-PadJ3)") (class "Default")
      (node (ref "U5") (pin "J3") (pinfunction "PG0/SDC1_CLK/PG_EINT0_J3") (pintype "passive+no_connect"))
    )
    (net (code "197") (name "unconnected-(U5-PG1{slash}SDC1_CMD{slash}PG_EINT1-PadL2)") (class "Default")
      (node (ref "U5") (pin "L2") (pinfunction "PG1/SDC1_CMD/PG_EINT1_L2") (pintype "passive+no_connect"))
    )
    (net (code "198") (name "unconnected-(U5-PG2{slash}SDC1_D0{slash}PG_EINT2-PadH4)") (class "Default")
      (node (ref "U5") (pin "H4") (pinfunction "PG2/SDC1_D0/PG_EINT2_H4") (pintype "passive+no_connect"))
    )
    (net (code "199") (name "unconnected-(U5-PG3{slash}SDC1_D1{slash}PG_EINT3-PadF3)") (class "Default")
      (node (ref "U5") (pin "F3") (pinfunction "PG3/SDC1_D1/PG_EINT3_F3") (pintype "passive+no_connect"))
    )
    (net (code "200") (name "unconnected-(U5-PG4{slash}SDC1_D2{slash}PG_EINT4-PadC2)") (class "Default")
      (node (ref "U5") (pin "C2") (pinfunction "PG4/SDC1_D2/PG_EINT4_C2") (pintype "passive+no_connect"))
    )
    (net (code "201") (name "unconnected-(U5-PG5{slash}SDC1_D3{slash}PG_EINT5-PadC1)") (class "Default")
      (node (ref "U5") (pin "C1") (pinfunction "PG5/SDC1_D3/PG_EINT5_C1") (pintype "passive+no_connect"))
    )
    (net (code "202") (name "unconnected-(U5-PG8{slash}UART1_RTS{slash}PG_EINT8-PadC3)") (class "Default")
      (node (ref "U5") (pin "C3") (pinfunction "PG8/UART1_RTS/PG_EINT8_C3") (pintype "passive+no_connect"))
    )
    (net (code "203") (name "unconnected-(U5-PG9{slash}UART1_CTS{slash}PG_EINT9-PadE3)") (class "Default")
      (node (ref "U5") (pin "E3") (pinfunction "PG9/UART1_CTS/PG_EINT9_E3") (pintype "passive+no_connect"))
    )
    (net (code "204") (name "unconnected-(U5-PG10{slash}PCM1_SYNC{slash}PG_EINT10-PadM3)") (class "Default")
      (node (ref "U5") (pin "M3") (pinfunction "PG10/PCM1_SYNC/PG_EINT10_M3") (pintype "passive+no_connect"))
    )
    (net (code "205") (name "unconnected-(U5-PG13{slash}PCM1_DIN{slash}PG_EINT13-PadB1)") (class "Default")
      (node (ref "U5") (pin "B1") (pinfunction "PG13/PCM1_DIN/PG_EINT13_B1") (pintype "passive+no_connect"))
    )
    (net (code "206") (name "unconnected-(U5-PL0{slash}S_TWI_SCK{slash}S_PL_EINT0-PadN1)") (class "Default")
      (node (ref "U5") (pin "N1") (pinfunction "PL0/S_TWI_SCK/S_PL_EINT0_N1") (pintype "passive+no_connect"))
    )
    (net (code "207") (name "unconnected-(U5-PL1{slash}S_TWI_SDA{slash}S_PL_EINT1-PadM1)") (class "Default")
      (node (ref "U5") (pin "M1") (pinfunction "PL1/S_TWI_SDA/S_PL_EINT1_M1") (pintype "passive+no_connect"))
    )
    (net (code "208") (name "unconnected-(U5-PL2{slash}S_UART_TX{slash}S_PL_EINT2-PadP2)") (class "Default")
      (node (ref "U5") (pin "P2") (pinfunction "PL2/S_UART_TX/S_PL_EINT2_P2") (pintype "passive+no_connect"))
    )
    (net (code "209") (name "unconnected-(U5-PL5{slash}S_JTAG_CK{slash}S_PL_EINT5-PadR2)") (class "Default")
      (node (ref "U5") (pin "R2") (pinfunction "PL5/S_JTAG_CK/S_PL_EINT5_R2") (pintype "passive+no_connect"))
    )
    (net (code "210") (name "unconnected-(U5-PL6{slash}S_JTAG_DO{slash}S_PL_EINT6-PadT4)") (class "Default")
      (node (ref "U5") (pin "T4") (pinfunction "PL6/S_JTAG_DO/S_PL_EINT6_T4") (pintype "passive+no_connect"))
    )
    (net (code "211") (name "unconnected-(U5-PL7{slash}S_JTAG_DI{slash}S_PL_EINT7-PadT3)") (class "Default")
      (node (ref "U5") (pin "T3") (pinfunction "PL7/S_JTAG_DI/S_PL_EINT7_T3") (pintype "passive+no_connect"))
    )
    (net (code "212") (name "unconnected-(U5-PLLTEST-PadL5)") (class "Default")
      (node (ref "U5") (pin "L5") (pinfunction "PLLTEST_L5") (pintype "passive+no_connect"))
    )
    (net (code "213") (name "unconnected-(U5-SDQ16-PadY17)") (class "Default")
      (node (ref "U5") (pin "Y17") (pinfunction "SDQ16_Y17") (pintype "passive+no_connect"))
    )
    (net (code "214") (name "unconnected-(U5-SDQ17-PadAA17)") (class "Default")
      (node (ref "U5") (pin "AA17") (pinfunction "SDQ17_AA17") (pintype "passive+no_connect"))
    )
    (net (code "215") (name "unconnected-(U5-SDQ18-PadY16)") (class "Default")
      (node (ref "U5") (pin "Y16") (pinfunction "SDQ18_Y16") (pintype "passive+no_connect"))
    )
    (net (code "216") (name "unconnected-(U5-SDQ19-PadW15)") (class "Default")
      (node (ref "U5") (pin "W15") (pinfunction "SDQ19_W15") (pintype "passive+no_connect"))
    )
    (net (code "217") (name "unconnected-(U5-SDQ20-PadY14)") (class "Default")
      (node (ref "U5") (pin "Y14") (pinfunction "SDQ20_Y14") (pintype "passive+no_connect"))
    )
    (net (code "218") (name "unconnected-(U5-SDQ21-PadAA14)") (class "Default")
      (node (ref "U5") (pin "AA14") (pinfunction "SDQ21_AA14") (pintype "passive+no_connect"))
    )
    (net (code "219") (name "unconnected-(U5-SDQ22-PadY13)") (class "Default")
      (node (ref "U5") (pin "Y13") (pinfunction "SDQ22_Y13") (pintype "passive+no_connect"))
    )
    (net (code "220") (name "unconnected-(U5-SDQ23-PadY12)") (class "Default")
      (node (ref "U5") (pin "Y12") (pinfunction "SDQ23_Y12") (pintype "passive+no_connect"))
    )
    (net (code "221") (name "unconnected-(U5-SDQ24-PadW12)") (class "Default")
      (node (ref "U5") (pin "W12") (pinfunction "SDQ24_W12") (pintype "passive+no_connect"))
    )
    (net (code "222") (name "unconnected-(U5-SDQ25-PadAA11)") (class "Default")
      (node (ref "U5") (pin "AA11") (pinfunction "SDQ25_AA11") (pintype "passive+no_connect"))
    )
    (net (code "223") (name "unconnected-(U5-SDQ26-PadY11)") (class "Default")
      (node (ref "U5") (pin "Y11") (pinfunction "SDQ26_Y11") (pintype "passive+no_connect"))
    )
    (net (code "224") (name "unconnected-(U5-SDQ27-PadY10)") (class "Default")
      (node (ref "U5") (pin "Y10") (pinfunction "SDQ27_Y10") (pintype "passive+no_connect"))
    )
    (net (code "225") (name "unconnected-(U5-SDQ28-PadW9)") (class "Default")
      (node (ref "U5") (pin "W9") (pinfunction "SDQ28_W9") (pintype "passive+no_connect"))
    )
    (net (code "226") (name "unconnected-(U5-SDQ29-PadAA8)") (class "Default")
      (node (ref "U5") (pin "AA8") (pinfunction "SDQ29_AA8") (pintype "passive+no_connect"))
    )
    (net (code "227") (name "unconnected-(U5-SDQ30-PadY8)") (class "Default")
      (node (ref "U5") (pin "Y8") (pinfunction "SDQ30_Y8") (pintype "passive+no_connect"))
    )
    (net (code "228") (name "unconnected-(U5-SDQ31-PadY7)") (class "Default")
      (node (ref "U5") (pin "Y7") (pinfunction "SDQ31_Y7") (pintype "passive+no_connect"))
    )
    (net (code "229") (name "unconnected-(U5-SDQM2-PadAA18)") (class "Default")
      (node (ref "U5") (pin "AA18") (pinfunction "SDQM2_AA18") (pintype "output"))
    )
    (net (code "230") (name "unconnected-(U5-SDQM3-PadAA12)") (class "Default")
      (node (ref "U5") (pin "AA12") (pinfunction "SDQM3_AA12") (pintype "output"))
    )
    (net (code "231") (name "unconnected-(U5-SDQS2-PadAA15)") (class "Default")
      (node (ref "U5") (pin "AA15") (pinfunction "SDQS2_AA15") (pintype "passive"))
    )
    (net (code "232") (name "unconnected-(U5-SDQS2B-PadY15)") (class "Default")
      (node (ref "U5") (pin "Y15") (pinfunction "SDQS2B_Y15") (pintype "passive"))
    )
    (net (code "233") (name "unconnected-(U5-SDQS3-PadAA9)") (class "Default")
      (node (ref "U5") (pin "AA9") (pinfunction "SDQS3_AA9") (pintype "passive"))
    )
    (net (code "234") (name "unconnected-(U5-SDQS3B-PadY9)") (class "Default")
      (node (ref "U5") (pin "Y9") (pinfunction "SDQS3B_Y9") (pintype "passive"))
    )
    (net (code "235") (name "unconnected-(U5-TEST-PadT5)") (class "Default")
      (node (ref "U5") (pin "T5") (pinfunction "TEST_T5") (pintype "passive+no_connect"))
    )
    (net (code "236") (name "unconnected-(U5-TVOUT-PadF10)") (class "Default")
      (node (ref "U5") (pin "F10") (pinfunction "TVOUT_F10") (pintype "output+no_connect"))
    )
    (net (code "237") (name "unconnected-(U5-X32KFOUT-PadP3)") (class "Default")
      (node (ref "U5") (pin "P3") (pinfunction "X32KFOUT_P3") (pintype "output+no_connect"))
    )
    (net (code "238") (name "unconnected-(U5-X32KIN-PadV5)") (class "Default")
      (node (ref "U5") (pin "V5") (pinfunction "X32KIN_V5") (pintype "passive+no_connect"))
    )
    (net (code "239") (name "unconnected-(U5-X32KOUT-PadU4)") (class "Default")
      (node (ref "U5") (pin "U4") (pinfunction "X32KOUT_U4") (pintype "output+no_connect"))
    )
  )
)
